# pandaLight.net
KiCad netlist of a schematic drawn in EAGLE
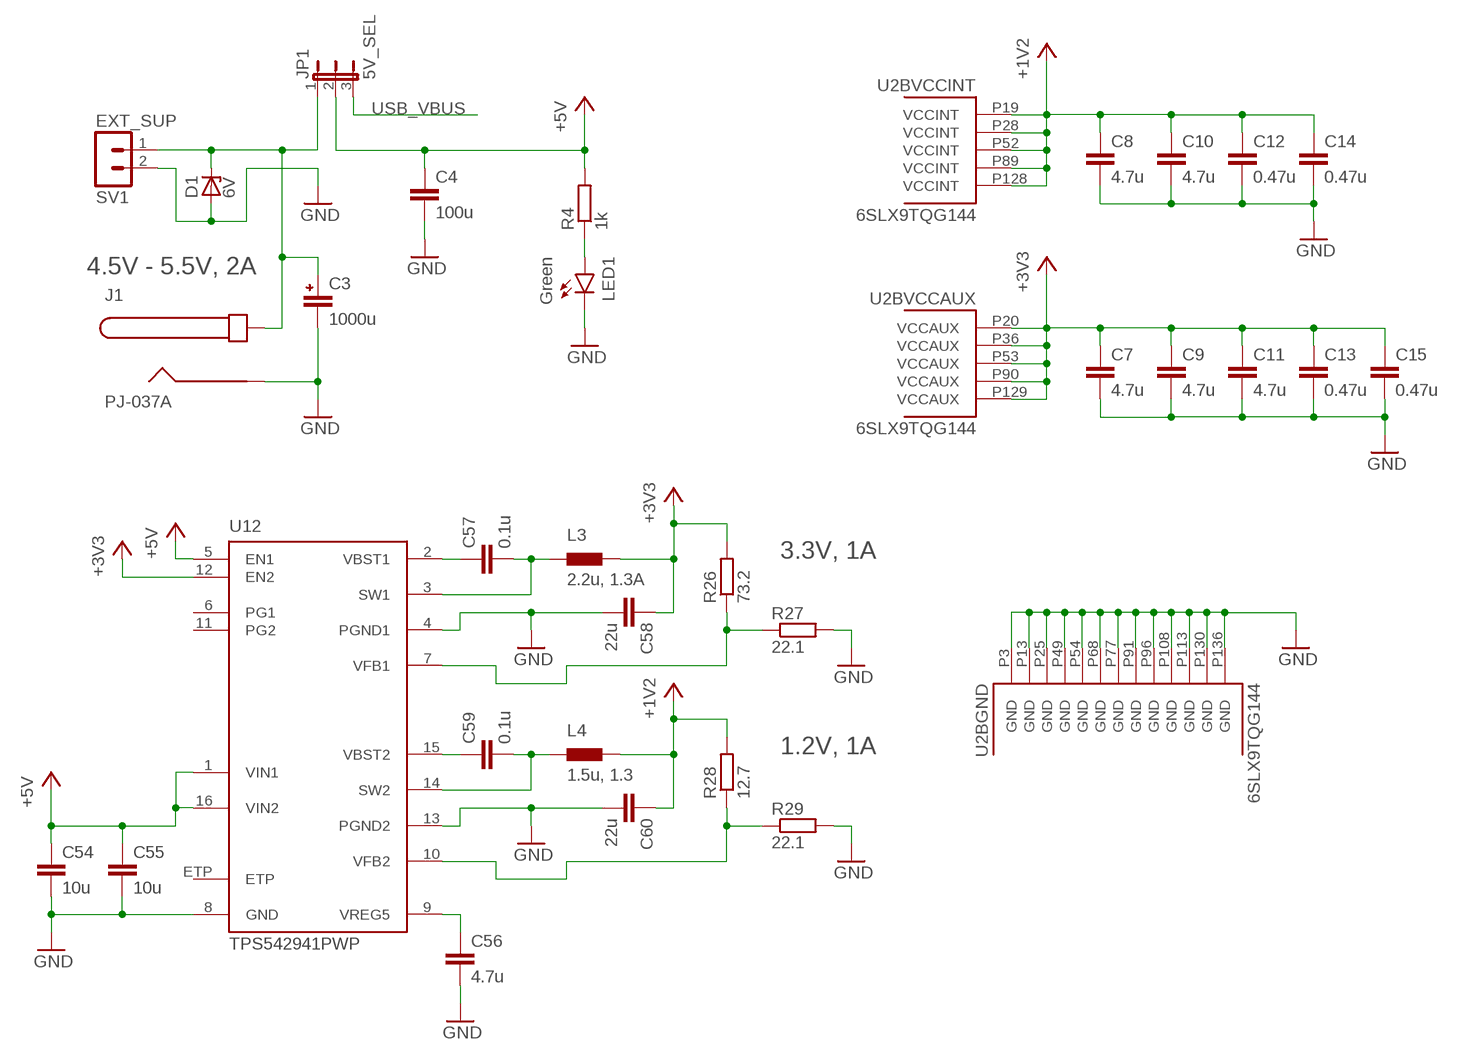
[diagram p0: schematic, sheet 1]
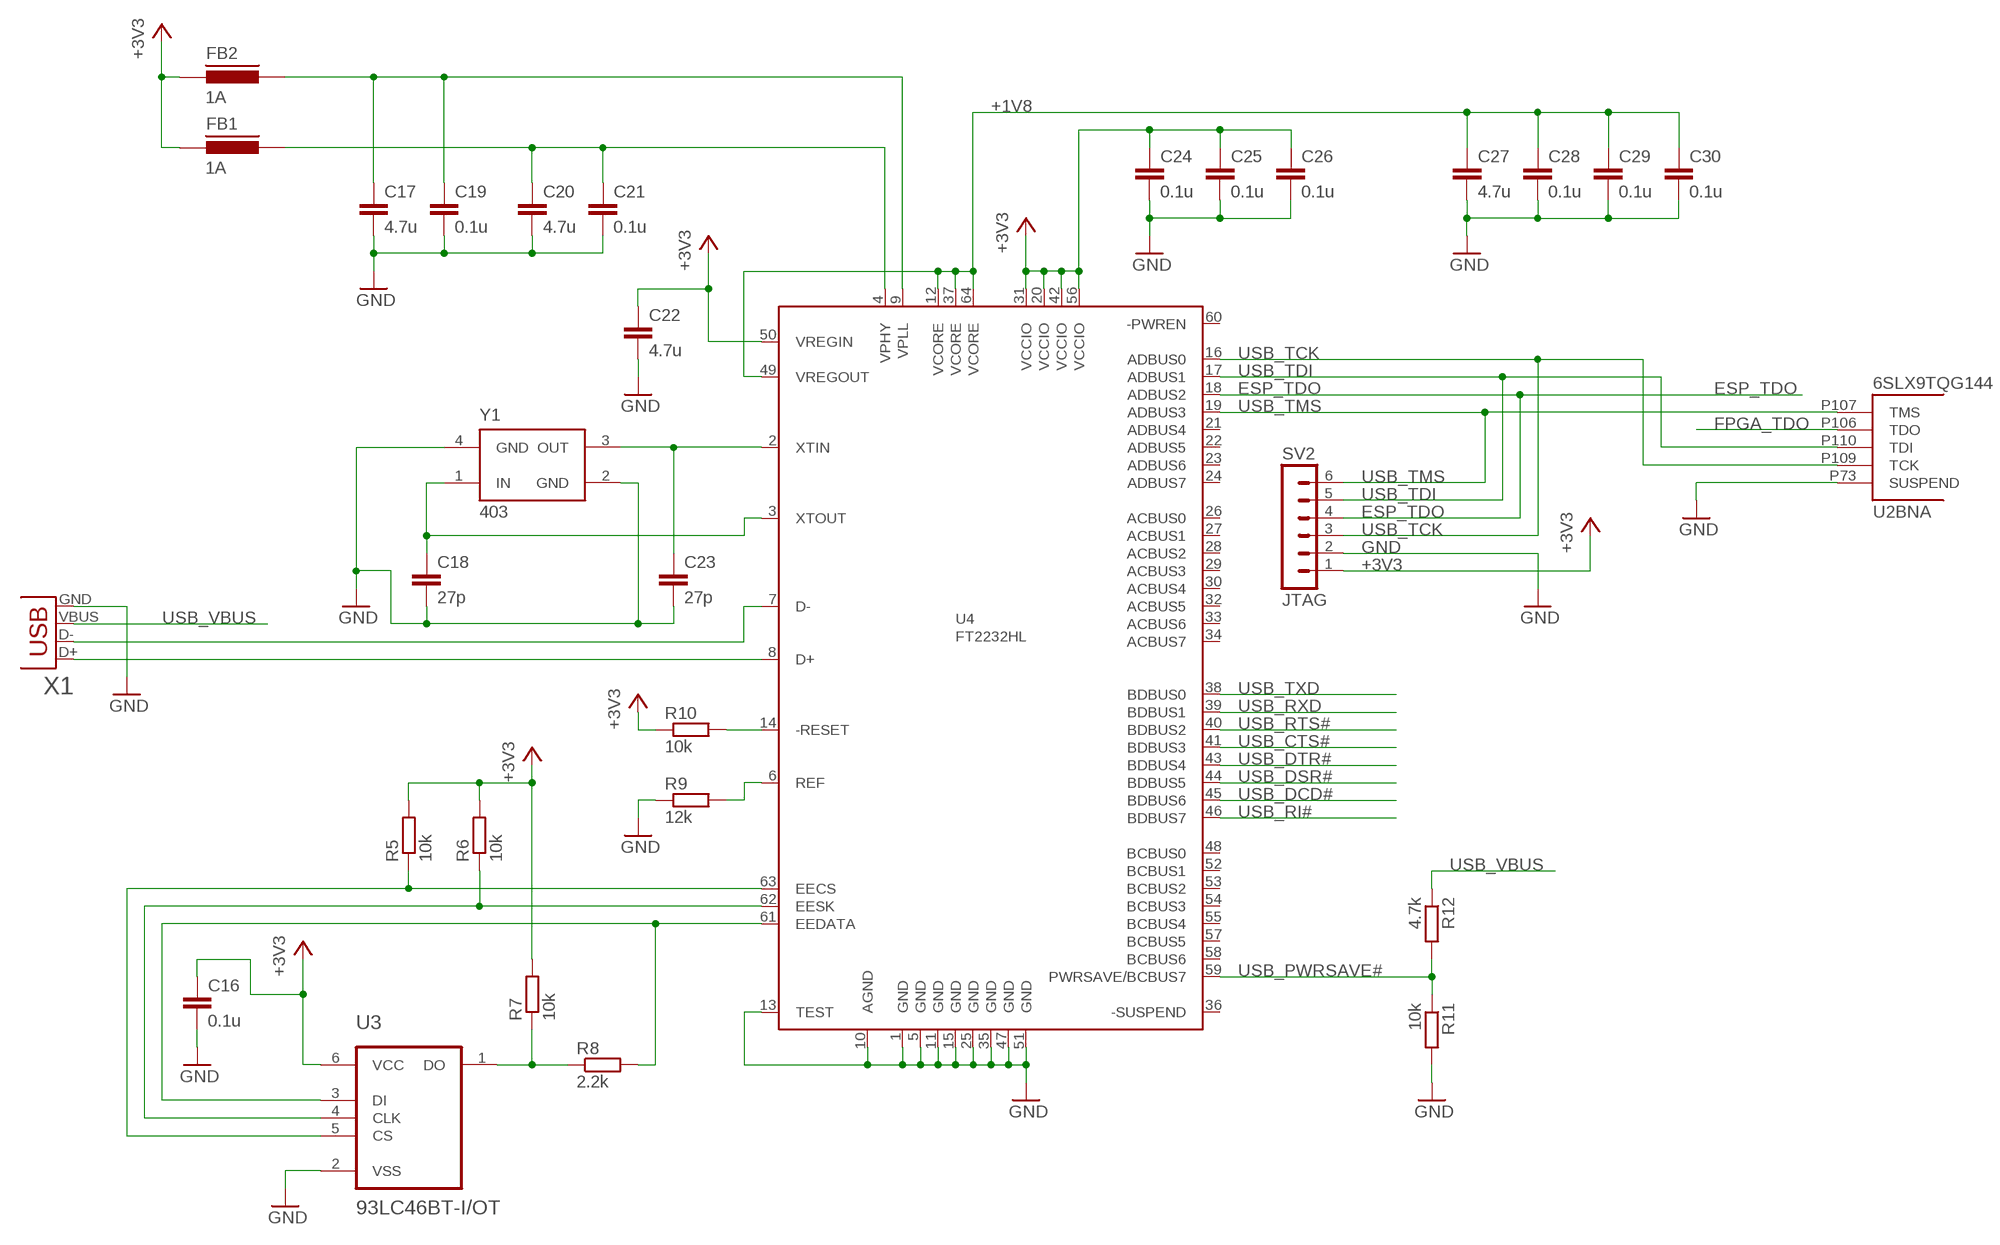
[diagram p1: schematic, sheet 2]
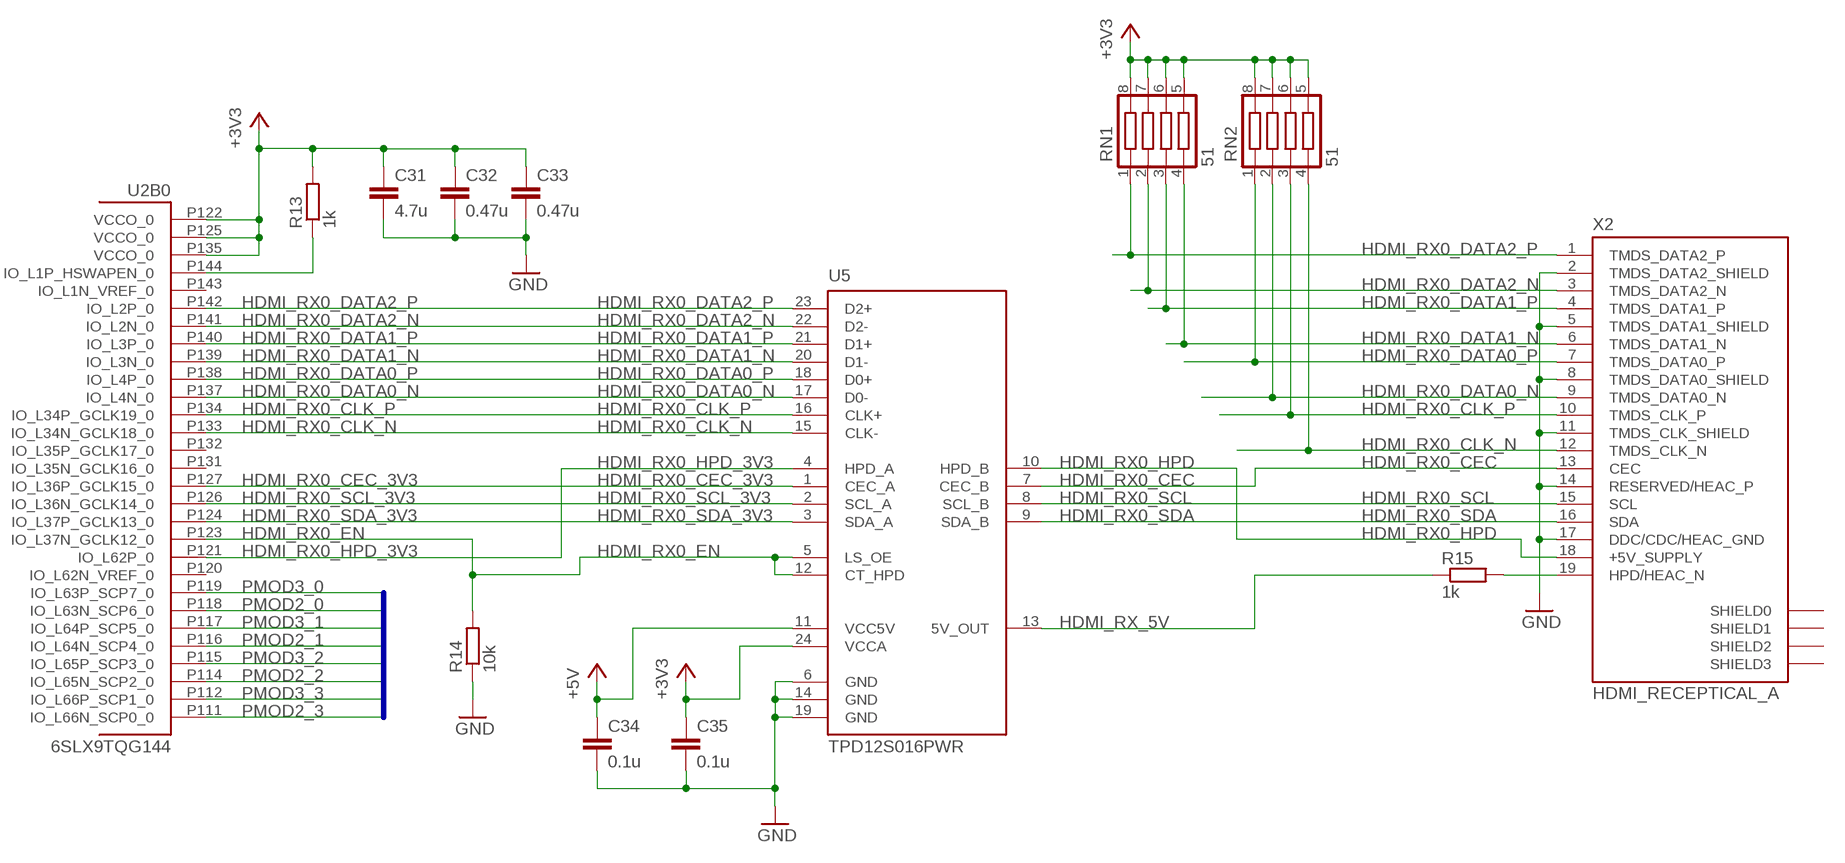
[diagram p2: schematic, sheet 3]
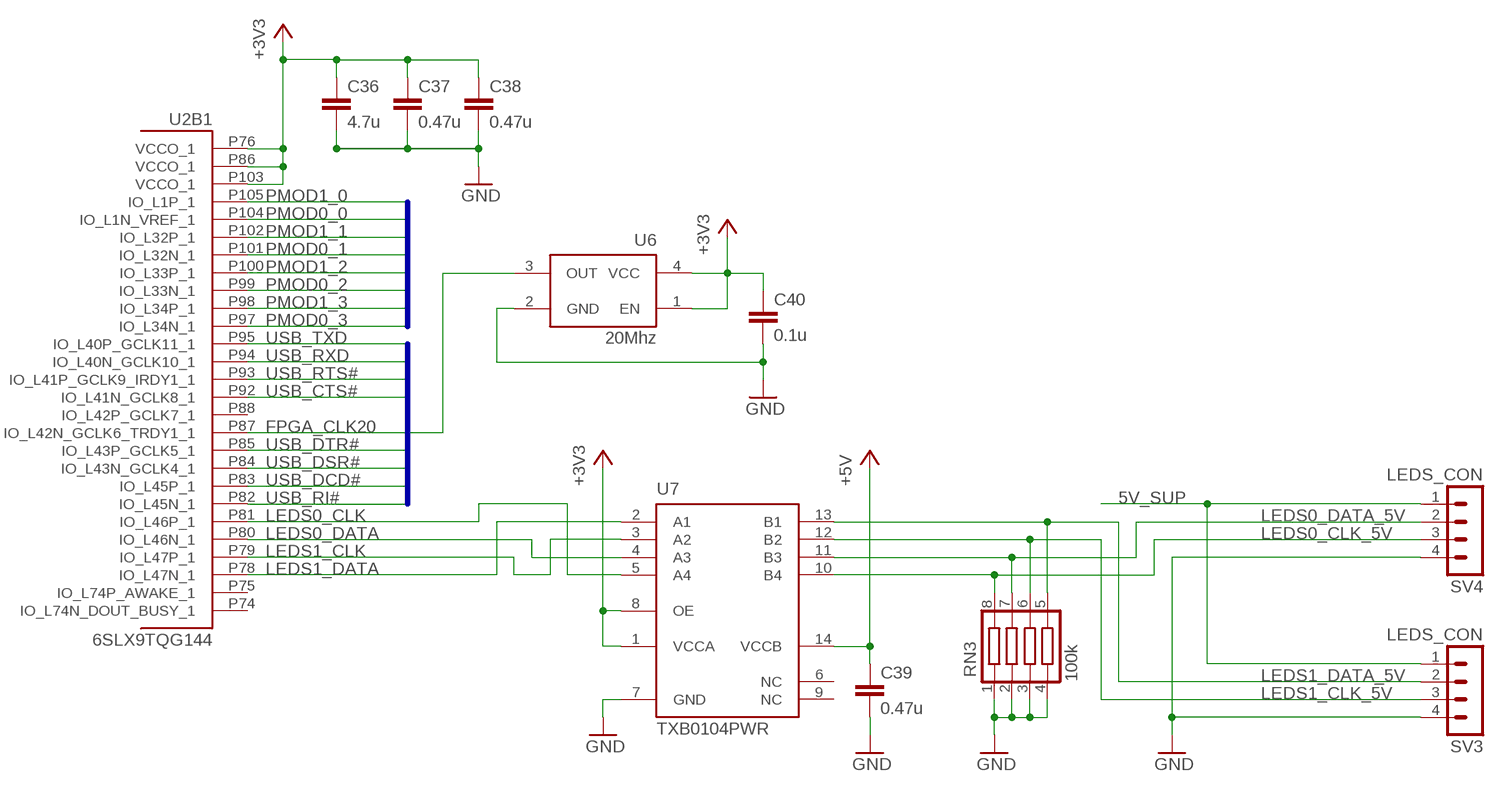
[diagram p3: schematic, sheet 4]
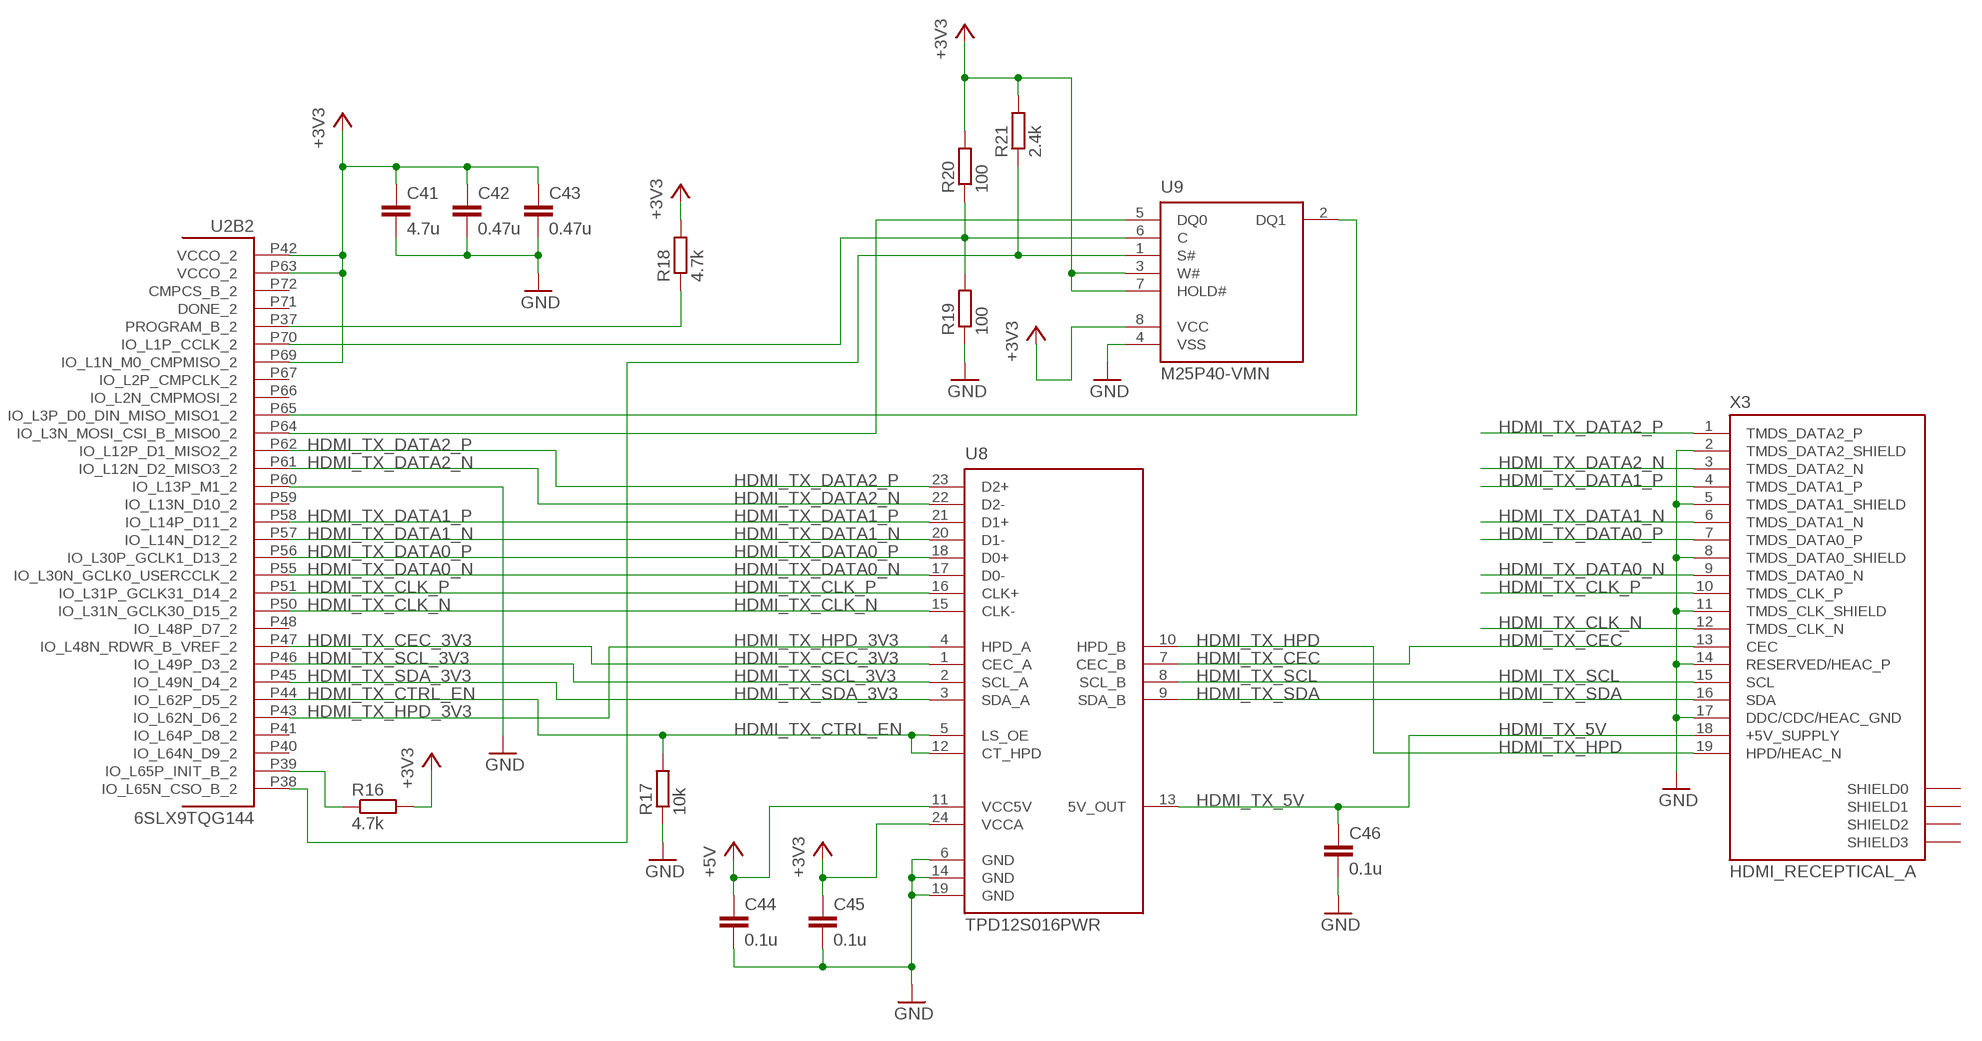
[diagram p4: schematic, sheet 5]
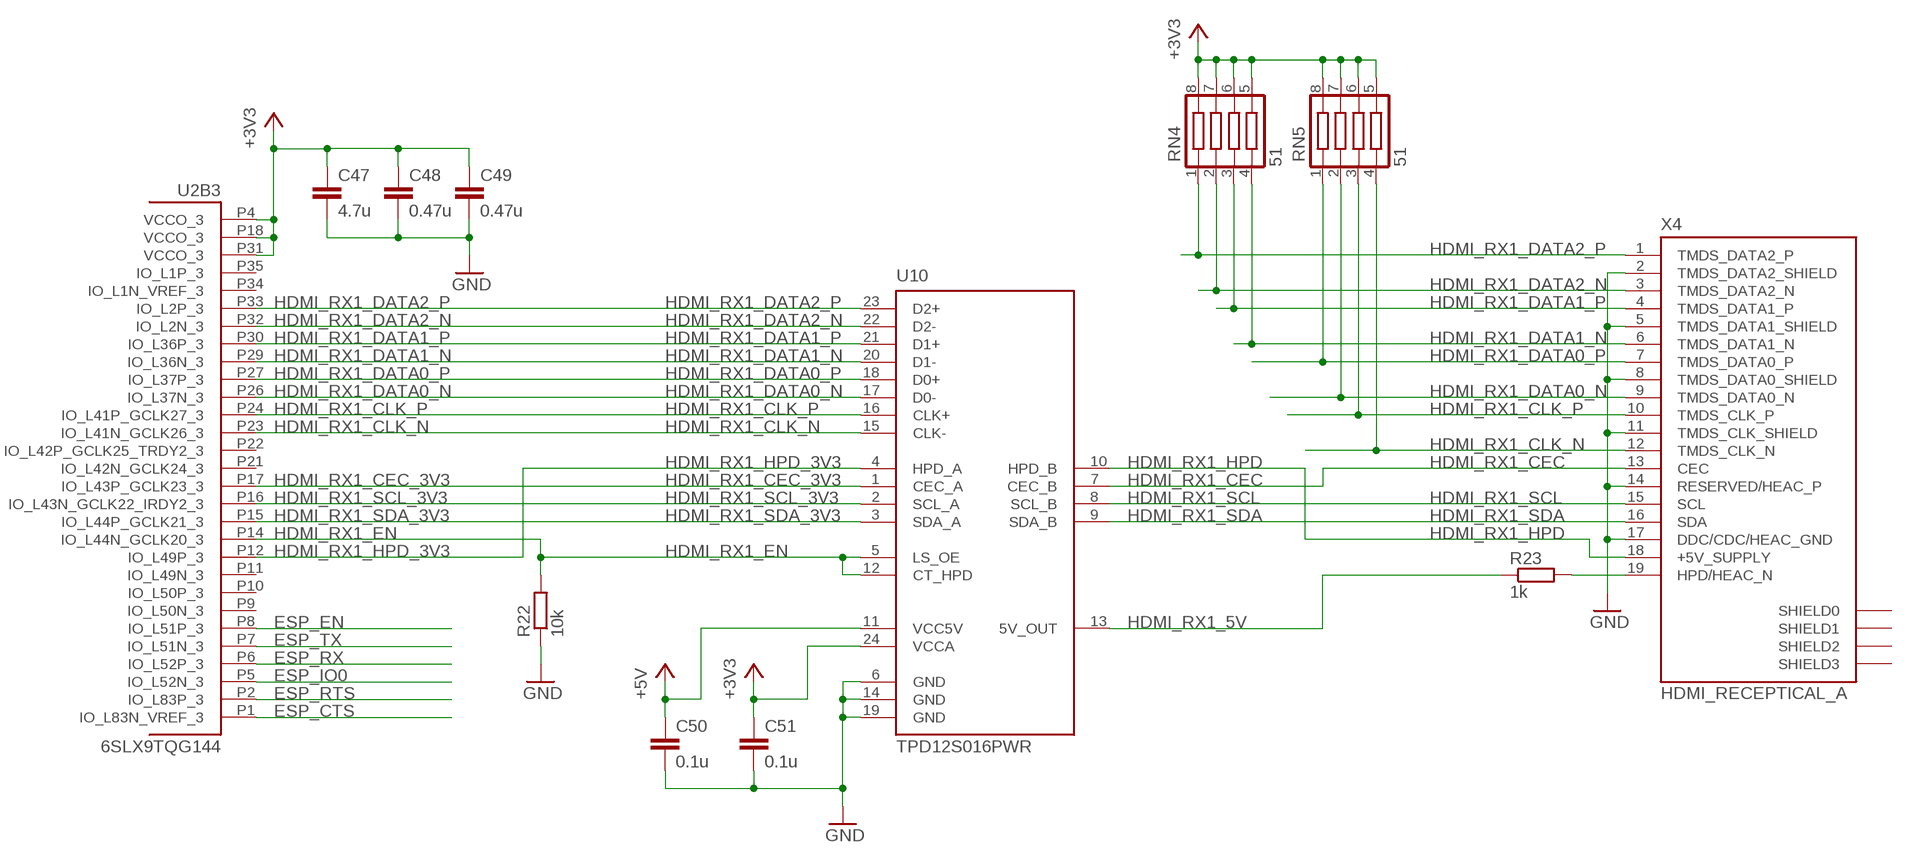
[diagram p5: schematic, sheet 6]
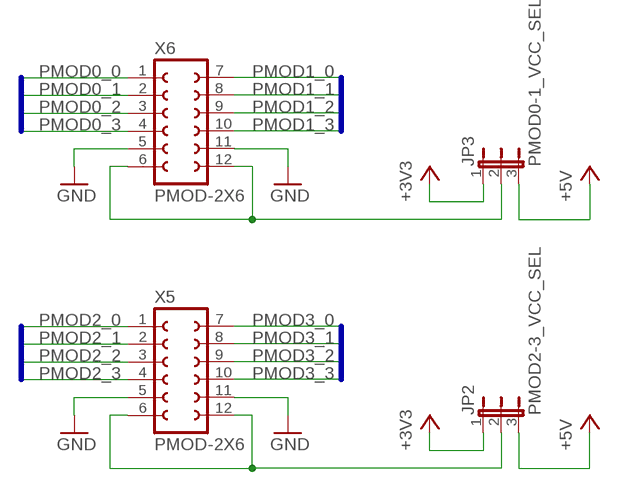
[diagram p6: schematic, sheet 7]
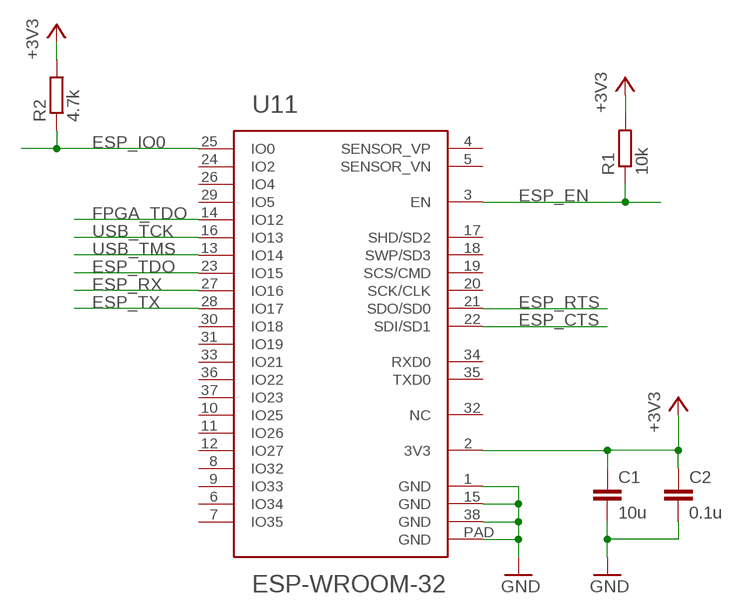
[diagram p7: schematic, sheet 8]
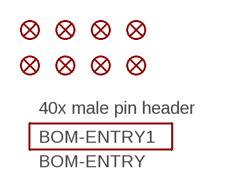
[diagram p8: schematic, sheet 9]

(export (version "E")
  (design (tool "Eeschema 10.0.6"))
  (components
    (comp (ref "C36")
      (value "4.7u")
      (footprint "eagle-import:C0603")
      (fields (field (name "PARTNO") "C0603C475K9PACTU"))
      (libsource (lib "eagle-import") (part "CAPACITOR0603"))
    )
    (comp (ref "C37")
      (value "0.47u")
      (footprint "eagle-import:C0402")
      (fields (field (name "PARTNO") "C1005X5R0J474K050BB"))
      (libsource (lib "eagle-import") (part "CAPACITOR0402"))
    )
    (comp (ref "C38")
      (value "0.47u")
      (footprint "eagle-import:C0402")
      (fields (field (name "PARTNO") "C1005X5R0J474K050BB"))
      (libsource (lib "eagle-import") (part "CAPACITOR0402"))
    )
    (comp (ref "C39")
      (value "0.47u")
      (footprint "eagle-import:C0402")
      (fields (field (name "PARTNO") "C1005X5R0J474K050BB"))
      (libsource (lib "eagle-import") (part "CAPACITOR0402"))
    )
    (comp (ref "C40")
      (value "0.1u")
      (footprint "eagle-import:C0402")
      (fields (field (name "PARTNO") "CL05B104KP5NNNC"))
      (libsource (lib "eagle-import") (part "CAPACITOR0402"))
    )
    (comp (ref "RN3")
      (value "100k")
      (footprint "eagle-import:741C083")
      (fields (field (name "PARTNO") "741C083104JP"))
      (libsource (lib "eagle-import") (part "741C083"))
    )
    (comp (ref "SV3")
      (value "LEDS_CON")
      (footprint "eagle-import:MA04-1")
      (libsource (lib "eagle-import") (part "MA04-1"))
    )
    (comp (ref "SV4")
      (value "LEDS_CON")
      (footprint "eagle-import:MA04-1")
      (libsource (lib "eagle-import") (part "MA04-1"))
    )
    (comp (ref "U2")
      (value "6SLX9TQG144")
      (footprint "eagle-import:TQ144")
      (fields (field (name "PARTNO") "XC6SLX9-3TQG144C"))
      (libsource (lib "eagle-import") (part "6SLX9TQG144"))
    )
    (comp (ref "U6")
      (value "20Mhz")
      (footprint "eagle-import:OSCI-1.6X1.2")
      (fields (field (name "PARTNO") "ASCO-20.000MHZ-EK-T3"))
      (libsource (lib "eagle-import") (part "OSCILLATOR"))
    )
    (comp (ref "U7")
      (value "TXB0104PWR")
      (footprint "eagle-import:R-PDSO-G14")
      (libsource (lib "eagle-import") (part "TXB0104PWR"))
    )
    (comp (ref "C41")
      (value "4.7u")
      (footprint "eagle-import:C0603")
      (fields (field (name "PARTNO") "C0603C475K9PACTU"))
      (libsource (lib "eagle-import") (part "CAPACITOR0603"))
    )
    (comp (ref "C42")
      (value "0.47u")
      (footprint "eagle-import:C0402")
      (fields (field (name "PARTNO") "C1005X5R0J474K050BB"))
      (libsource (lib "eagle-import") (part "CAPACITOR0402"))
    )
    (comp (ref "C43")
      (value "0.47u")
      (footprint "eagle-import:C0402")
      (fields (field (name "PARTNO") "C1005X5R0J474K050BB"))
      (libsource (lib "eagle-import") (part "CAPACITOR0402"))
    )
    (comp (ref "C44")
      (value "0.1u")
      (footprint "eagle-import:C0402")
      (fields (field (name "PARTNO") "CL05B104KP5NNNC"))
      (libsource (lib "eagle-import") (part "CAPACITOR0402"))
    )
    (comp (ref "C45")
      (value "0.1u")
      (footprint "eagle-import:C0402")
      (fields (field (name "PARTNO") "CL05B104KP5NNNC"))
      (libsource (lib "eagle-import") (part "CAPACITOR0402"))
    )
    (comp (ref "C46")
      (value "0.1u")
      (footprint "eagle-import:C0402")
      (fields (field (name "PARTNO") "CL05B104KP5NNNC"))
      (libsource (lib "eagle-import") (part "CAPACITOR0402"))
    )
    (comp (ref "R16")
      (value "4.7k")
      (footprint "eagle-import:R0402")
      (fields (field (name "PARTNO") "ERJ-2RKF4701X"))
      (libsource (lib "eagle-import") (part "RESISTOR0402"))
    )
    (comp (ref "R17")
      (value "10k")
      (footprint "eagle-import:R0402")
      (fields (field (name "PARTNO") "ERJ-2RKF1002X"))
      (libsource (lib "eagle-import") (part "RESISTOR0402"))
    )
    (comp (ref "R18")
      (value "4.7k")
      (footprint "eagle-import:R0402")
      (fields (field (name "PARTNO") "ERJ-2RKF4701X"))
      (libsource (lib "eagle-import") (part "RESISTOR0402"))
    )
    (comp (ref "R19")
      (value "100")
      (footprint "eagle-import:R0402")
      (fields (field (name "PARTNO") "ERJ-2GEJ101X"))
      (libsource (lib "eagle-import") (part "RESISTOR0402"))
    )
    (comp (ref "R20")
      (value "100")
      (footprint "eagle-import:R0402")
      (fields (field (name "PARTNO") "ERJ-2GEJ101X"))
      (libsource (lib "eagle-import") (part "RESISTOR0402"))
    )
    (comp (ref "R21")
      (value "2.4k")
      (footprint "eagle-import:R0402")
      (fields (field (name "PARTNO") "ERJ-2RKF2401X"))
      (libsource (lib "eagle-import") (part "RESISTOR0402"))
    )
    (comp (ref "U8")
      (value "TPD12S016PWR")
      (footprint "eagle-import:PW_R-PDSO-G24")
      (libsource (lib "eagle-import") (part "TPD12S016PWR"))
    )
    (comp (ref "U9")
      (value "M25P40-VMN")
      (footprint "eagle-import:SO8N")
      (fields (field (name "PARTNO") "M25P80-VMN6TP"))
      (libsource (lib "eagle-import") (part "M25P40-VMN"))
    )
    (comp (ref "X3")
      (value "HDMI_RECEPTICAL_A")
      (footprint "eagle-import:HDMI_TYPE_A_RECEPTICAL")
      (fields (field (name "PARTNO") "10029449-111RLF"))
      (libsource (lib "eagle-import") (part "HDMI_RECEPTICAL_A"))
    )
    (comp (ref "FID1")
      (value "FIDUCIAL1X2")
      (footprint "eagle-import:FIDUCIAL-1X2")
      (libsource (lib "eagle-import") (part "FIDUCIAL1X2"))
    )
    (comp (ref "FID2")
      (value "FIDUCIAL1X2")
      (footprint "eagle-import:FIDUCIAL-1X2")
      (libsource (lib "eagle-import") (part "FIDUCIAL1X2"))
    )
    (comp (ref "FID3")
      (value "FIDUCIAL1X2")
      (footprint "eagle-import:FIDUCIAL-1X2")
      (libsource (lib "eagle-import") (part "FIDUCIAL1X2"))
    )
    (comp (ref "FID4")
      (value "FIDUCIAL1X2")
      (footprint "eagle-import:FIDUCIAL-1X2")
      (libsource (lib "eagle-import") (part "FIDUCIAL1X2"))
    )
    (comp (ref "FID5")
      (value "FIDUCIAL1X2")
      (footprint "eagle-import:FIDUCIAL-1X2")
      (libsource (lib "eagle-import") (part "FIDUCIAL1X2"))
    )
    (comp (ref "FID6")
      (value "FIDUCIAL1X2")
      (footprint "eagle-import:FIDUCIAL-1X2")
      (libsource (lib "eagle-import") (part "FIDUCIAL1X2"))
    )
    (comp (ref "FID7")
      (value "FIDUCIAL1X2")
      (footprint "eagle-import:FIDUCIAL-1X2")
      (libsource (lib "eagle-import") (part "FIDUCIAL1X2"))
    )
    (comp (ref "FID8")
      (value "FIDUCIAL1X2")
      (footprint "eagle-import:FIDUCIAL-1X2")
      (libsource (lib "eagle-import") (part "FIDUCIAL1X2"))
    )
    (comp (ref "C3")
      (value "1000u")
      (footprint "eagle-import:MVY_HA0")
      (fields (field (name "PARTNO") "EMVY6R3ADA102MHA0G"))
      (libsource (lib "eagle-import") (part "CAPACITOR_POL"))
    )
    (comp (ref "C4")
      (value "100u")
      (footprint "eagle-import:C1206")
      (fields (field (name "PARTNO") "CL31A107MQHNNNE"))
      (libsource (lib "eagle-import") (part "CAPACITOR1206"))
    )
    (comp (ref "C7")
      (value "4.7u")
      (footprint "eagle-import:C0603")
      (fields (field (name "PARTNO") "C0603C475K9PACTU"))
      (libsource (lib "eagle-import") (part "CAPACITOR0603"))
    )
    (comp (ref "C8")
      (value "4.7u")
      (footprint "eagle-import:C0603")
      (fields (field (name "PARTNO") "C0603C475K9PACTU"))
      (libsource (lib "eagle-import") (part "CAPACITOR0603"))
    )
    (comp (ref "C9")
      (value "4.7u")
      (footprint "eagle-import:C0603")
      (fields (field (name "PARTNO") "C0603C475K9PACTU"))
      (libsource (lib "eagle-import") (part "CAPACITOR0603"))
    )
    (comp (ref "C10")
      (value "4.7u")
      (footprint "eagle-import:C0603")
      (fields (field (name "PARTNO") "C0603C475K9PACTU"))
      (libsource (lib "eagle-import") (part "CAPACITOR0603"))
    )
    (comp (ref "C11")
      (value "4.7u")
      (footprint "eagle-import:C0603")
      (fields (field (name "PARTNO") "C0603C475K9PACTU"))
      (libsource (lib "eagle-import") (part "CAPACITOR0603"))
    )
    (comp (ref "C12")
      (value "0.47u")
      (footprint "eagle-import:C0402")
      (fields (field (name "PARTNO") "C1005X5R0J474K050BB"))
      (libsource (lib "eagle-import") (part "CAPACITOR0402"))
    )
    (comp (ref "C13")
      (value "0.47u")
      (footprint "eagle-import:C0402")
      (fields (field (name "PARTNO") "C1005X5R0J474K050BB"))
      (libsource (lib "eagle-import") (part "CAPACITOR0402"))
    )
    (comp (ref "C14")
      (value "0.47u")
      (footprint "eagle-import:C0402")
      (fields (field (name "PARTNO") "C1005X5R0J474K050BB"))
      (libsource (lib "eagle-import") (part "CAPACITOR0402"))
    )
    (comp (ref "C15")
      (value "0.47u")
      (footprint "eagle-import:C0402")
      (fields (field (name "PARTNO") "C1005X5R0J474K050BB"))
      (libsource (lib "eagle-import") (part "CAPACITOR0402"))
    )
    (comp (ref "C54")
      (value "10u")
      (footprint "eagle-import:C0603")
      (fields (field (name "PARTNO") "CL10A106MQ8NNNC"))
      (libsource (lib "eagle-import") (part "CAPACITOR0603"))
    )
    (comp (ref "C55")
      (value "10u")
      (footprint "eagle-import:C0603")
      (fields (field (name "PARTNO") "CL10A106MQ8NNNC"))
      (libsource (lib "eagle-import") (part "CAPACITOR0603"))
    )
    (comp (ref "C56")
      (value "4.7u")
      (footprint "eagle-import:C0603")
      (fields (field (name "PARTNO") "C0603C475K9PACTU"))
      (libsource (lib "eagle-import") (part "CAPACITOR0603"))
    )
    (comp (ref "C57")
      (value "0.1u")
      (footprint "eagle-import:C0402")
      (fields (field (name "PARTNO") "CL05B104KP5NNNC"))
      (libsource (lib "eagle-import") (part "CAPACITOR0402"))
    )
    (comp (ref "C58")
      (value "22u")
      (footprint "eagle-import:C0603")
      (fields (field (name "PARTNO") "CL10A226MQ8NRNC"))
      (libsource (lib "eagle-import") (part "CAPACITOR0603"))
    )
    (comp (ref "C59")
      (value "0.1u")
      (footprint "eagle-import:C0402")
      (fields (field (name "PARTNO") "CL05B104KP5NNNC"))
      (libsource (lib "eagle-import") (part "CAPACITOR0402"))
    )
    (comp (ref "C60")
      (value "22u")
      (footprint "eagle-import:C0603")
      (fields (field (name "PARTNO") "CL10A226MQ8NRNC"))
      (libsource (lib "eagle-import") (part "CAPACITOR0603"))
    )
    (comp (ref "D1")
      (value "6V")
      (footprint "eagle-import:DO-214AC")
      (fields (field (name "PARTNO") "SMAJ6.0A"))
      (libsource (lib "eagle-import") (part "ZENER_DIODE"))
    )
    (comp (ref "J1")
      (value "PJ-037A")
      (footprint "eagle-import:PJ-037A")
      (libsource (lib "eagle-import") (part "PJ-037A"))
    )
    (comp (ref "JP1")
      (value "5V_SEL")
      (footprint "eagle-import:JP2")
      (fields (field (name "PARTNO") "SPC02SYAN"))
      (libsource (lib "eagle-import") (part "JP2E"))
    )
    (comp (ref "L3")
      (value "2.2u, 1.3A")
      (footprint "eagle-import:SRN3015_3X3")
      (fields (field (name "PARTNO") "SRN3015-2R2M"))
      (libsource (lib "eagle-import") (part "SRN3015"))
    )
    (comp (ref "L4")
      (value "1.5u, 1.3")
      (footprint "eagle-import:SRN3015_3X3")
      (fields (field (name "PARTNO") "SRN3015-1R5Y"))
      (libsource (lib "eagle-import") (part "SRN3015"))
    )
    (comp (ref "LED1")
      (value "Green")
      (footprint "eagle-import:LED-0603")
      (fields (field (name "PARTNO") "LTST-C191KGKT"))
      (libsource (lib "eagle-import") (part "LED0603"))
    )
    (comp (ref "R4")
      (value "1k")
      (footprint "eagle-import:R0402")
      (fields (field (name "PARTNO") "ERJ-2RKF1001X"))
      (libsource (lib "eagle-import") (part "RESISTOR0402"))
    )
    (comp (ref "R26")
      (value "73.2")
      (footprint "eagle-import:R0402")
      (fields (field (name "PARTNO") "ERJ-2RKF73R2X"))
      (libsource (lib "eagle-import") (part "RESISTOR0402"))
    )
    (comp (ref "R27")
      (value "22.1")
      (footprint "eagle-import:R0402")
      (fields (field (name "PARTNO") "ERJ-2RKF22R1X"))
      (libsource (lib "eagle-import") (part "RESISTOR0402"))
    )
    (comp (ref "R28")
      (value "12.7")
      (footprint "eagle-import:R0402")
      (fields (field (name "PARTNO") "ERJ-2RKF12R7X"))
      (libsource (lib "eagle-import") (part "RESISTOR0402"))
    )
    (comp (ref "R29")
      (value "22.1")
      (footprint "eagle-import:R0402")
      (fields (field (name "PARTNO") "ERJ-2RKF22R1X"))
      (libsource (lib "eagle-import") (part "RESISTOR0402"))
    )
    (comp (ref "SV1")
      (value "EXT_SUP")
      (footprint "eagle-import:MA02-1")
      (libsource (lib "eagle-import") (part "MA02-1"))
    )
    (comp (ref "U12")
      (value "TPS542941PWP")
      (footprint "eagle-import:R-PDSO-G16")
      (libsource (lib "eagle-import") (part "TPS542941PWP"))
    )
    (comp (ref "C1")
      (value "10u")
      (footprint "eagle-import:C0603")
      (libsource (lib "eagle-import") (part "CAPACITOR0603"))
    )
    (comp (ref "C2")
      (value "0.1u")
      (footprint "eagle-import:C0402")
      (fields (field (name "PARTNO") "CL05B104KP5NNNC"))
      (libsource (lib "eagle-import") (part "CAPACITOR0402"))
    )
    (comp (ref "R1")
      (value "10k")
      (footprint "eagle-import:R0402")
      (fields (field (name "PARTNO") "ERJ-2RKF1002X"))
      (libsource (lib "eagle-import") (part "RESISTOR0402"))
    )
    (comp (ref "R2")
      (value "4.7k")
      (footprint "eagle-import:R0402")
      (fields (field (name "PARTNO") "ERJ-2RKF1002X"))
      (libsource (lib "eagle-import") (part "RESISTOR0402"))
    )
    (comp (ref "U11")
      (value "ESP-WROOM-32")
      (footprint "eagle-import:ESP-WROOM-32")
      (libsource (lib "eagle-import") (part "ESP-WROOM-32"))
    )
    (comp (ref "C31")
      (value "4.7u")
      (footprint "eagle-import:C0603")
      (fields (field (name "PARTNO") "C0603C475K9PACTU"))
      (libsource (lib "eagle-import") (part "CAPACITOR0603"))
    )
    (comp (ref "C32")
      (value "0.47u")
      (footprint "eagle-import:C0402")
      (fields (field (name "PARTNO") "C1005X5R0J474K050BB"))
      (libsource (lib "eagle-import") (part "CAPACITOR0402"))
    )
    (comp (ref "C33")
      (value "0.47u")
      (footprint "eagle-import:C0402")
      (fields (field (name "PARTNO") "C1005X5R0J474K050BB"))
      (libsource (lib "eagle-import") (part "CAPACITOR0402"))
    )
    (comp (ref "C34")
      (value "0.1u")
      (footprint "eagle-import:C0402")
      (fields (field (name "PARTNO") "CL05B104KP5NNNC"))
      (libsource (lib "eagle-import") (part "CAPACITOR0402"))
    )
    (comp (ref "C35")
      (value "0.1u")
      (footprint "eagle-import:C0402")
      (fields (field (name "PARTNO") "CL05B104KP5NNNC"))
      (libsource (lib "eagle-import") (part "CAPACITOR0402"))
    )
    (comp (ref "R13")
      (value "1k")
      (footprint "eagle-import:R0402")
      (fields (field (name "PARTNO") "ERJ-2RKF1001X"))
      (libsource (lib "eagle-import") (part "RESISTOR0402"))
    )
    (comp (ref "R14")
      (value "10k")
      (footprint "eagle-import:R0402")
      (fields (field (name "PARTNO") "ERJ-2RKF1002X"))
      (libsource (lib "eagle-import") (part "RESISTOR0402"))
    )
    (comp (ref "R15")
      (value "1k")
      (footprint "eagle-import:R0402")
      (fields (field (name "PARTNO") "ERJ-2RKF1001X"))
      (libsource (lib "eagle-import") (part "RESISTOR0402"))
    )
    (comp (ref "RN1")
      (value "51")
      (footprint "eagle-import:741C083")
      (fields (field (name "PARTNO") "741C083510JP"))
      (libsource (lib "eagle-import") (part "741C083"))
    )
    (comp (ref "RN2")
      (value "51")
      (footprint "eagle-import:741C083")
      (fields (field (name "PARTNO") "741C083510JP"))
      (libsource (lib "eagle-import") (part "741C083"))
    )
    (comp (ref "U5")
      (value "TPD12S016PWR")
      (footprint "eagle-import:PW_R-PDSO-G24")
      (libsource (lib "eagle-import") (part "TPD12S016PWR"))
    )
    (comp (ref "X2")
      (value "HDMI_RECEPTICAL_A")
      (footprint "eagle-import:HDMI_TYPE_A_RECEPTICAL")
      (fields (field (name "PARTNO") "10029449-111RLF"))
      (libsource (lib "eagle-import") (part "HDMI_RECEPTICAL_A"))
    )
    (comp (ref "C47")
      (value "4.7u")
      (footprint "eagle-import:C0603")
      (fields (field (name "PARTNO") "C0603C475K9PACTU"))
      (libsource (lib "eagle-import") (part "CAPACITOR0603"))
    )
    (comp (ref "C48")
      (value "0.47u")
      (footprint "eagle-import:C0402")
      (fields (field (name "PARTNO") "C1005X5R0J474K050BB"))
      (libsource (lib "eagle-import") (part "CAPACITOR0402"))
    )
    (comp (ref "C49")
      (value "0.47u")
      (footprint "eagle-import:C0402")
      (fields (field (name "PARTNO") "C1005X5R0J474K050BB"))
      (libsource (lib "eagle-import") (part "CAPACITOR0402"))
    )
    (comp (ref "C50")
      (value "0.1u")
      (footprint "eagle-import:C0402")
      (fields (field (name "PARTNO") "CL05B104KP5NNNC"))
      (libsource (lib "eagle-import") (part "CAPACITOR0402"))
    )
    (comp (ref "C51")
      (value "0.1u")
      (footprint "eagle-import:C0402")
      (fields (field (name "PARTNO") "CL05B104KP5NNNC"))
      (libsource (lib "eagle-import") (part "CAPACITOR0402"))
    )
    (comp (ref "R22")
      (value "10k")
      (footprint "eagle-import:R0402")
      (fields (field (name "PARTNO") "ERJ-2RKF1002X"))
      (libsource (lib "eagle-import") (part "RESISTOR0402"))
    )
    (comp (ref "R23")
      (value "1k")
      (footprint "eagle-import:R0402")
      (fields (field (name "PARTNO") "ERJ-2RKF1001X"))
      (libsource (lib "eagle-import") (part "RESISTOR0402"))
    )
    (comp (ref "RN4")
      (value "51")
      (footprint "eagle-import:741C083")
      (fields (field (name "PARTNO") "741C083510JP"))
      (libsource (lib "eagle-import") (part "741C083"))
    )
    (comp (ref "RN5")
      (value "51")
      (footprint "eagle-import:741C083")
      (fields (field (name "PARTNO") "741C083510JP"))
      (libsource (lib "eagle-import") (part "741C083"))
    )
    (comp (ref "U10")
      (value "TPD12S016PWR")
      (footprint "eagle-import:PW_R-PDSO-G24")
      (libsource (lib "eagle-import") (part "TPD12S016PWR"))
    )
    (comp (ref "X4")
      (value "HDMI_RECEPTICAL_A")
      (footprint "eagle-import:HDMI_TYPE_A_RECEPTICAL")
      (fields (field (name "PARTNO") "10029449-111RLF"))
      (libsource (lib "eagle-import") (part "HDMI_RECEPTICAL_A"))
    )
    (comp (ref "JP2")
      (value "PMOD2-3_VCC_SEL")
      (footprint "eagle-import:JP2")
      (fields (field (name "PARTNO") "SPC02SYAN"))
      (libsource (lib "eagle-import") (part "JP2E"))
    )
    (comp (ref "JP3")
      (value "PMOD0-1_VCC_SEL")
      (footprint "eagle-import:JP2")
      (fields (field (name "PARTNO") "SPC02SYAN"))
      (libsource (lib "eagle-import") (part "JP2E"))
    )
    (comp (ref "X5")
      (value "PMOD-2X6")
      (footprint "eagle-import:PMOD-2X6")
      (fields (field (name "PARTNO") "PPTC062LJBN-RC"))
      (libsource (lib "eagle-import") (part "PMOD-2X6"))
    )
    (comp (ref "X6")
      (value "PMOD-2X6")
      (footprint "eagle-import:PMOD-2X6")
      (fields (field (name "PARTNO") "PPTC062LJBN-RC"))
      (libsource (lib "eagle-import") (part "PMOD-2X6"))
    )
    (comp (ref "C16")
      (value "0.1u")
      (footprint "eagle-import:C0402")
      (fields (field (name "PARTNO") "CL05B104KP5NNNC"))
      (libsource (lib "eagle-import") (part "CAPACITOR0402"))
    )
    (comp (ref "C17")
      (value "4.7u")
      (footprint "eagle-import:C0603")
      (fields (field (name "PARTNO") "C0603C475K9PACTU"))
      (libsource (lib "eagle-import") (part "CAPACITOR0603"))
    )
    (comp (ref "C18")
      (value "27p")
      (footprint "eagle-import:C0402")
      (fields (field (name "PARTNO") "CL05C270JB5NNNC"))
      (libsource (lib "eagle-import") (part "CAPACITOR0402"))
    )
    (comp (ref "C19")
      (value "0.1u")
      (footprint "eagle-import:C0402")
      (fields (field (name "PARTNO") "CL05B104KP5NNNC"))
      (libsource (lib "eagle-import") (part "CAPACITOR0402"))
    )
    (comp (ref "C20")
      (value "4.7u")
      (footprint "eagle-import:C0603")
      (fields (field (name "PARTNO") "C0603C475K9PACTU"))
      (libsource (lib "eagle-import") (part "CAPACITOR0603"))
    )
    (comp (ref "C21")
      (value "0.1u")
      (footprint "eagle-import:C0402")
      (fields (field (name "PARTNO") "CL05B104KP5NNNC"))
      (libsource (lib "eagle-import") (part "CAPACITOR0402"))
    )
    (comp (ref "C22")
      (value "4.7u")
      (footprint "eagle-import:C0603")
      (fields (field (name "PARTNO") "C0603C475K9PACTU"))
      (libsource (lib "eagle-import") (part "CAPACITOR0603"))
    )
    (comp (ref "C23")
      (value "27p")
      (footprint "eagle-import:C0402")
      (fields (field (name "PARTNO") "CL05C270JB5NNNC"))
      (libsource (lib "eagle-import") (part "CAPACITOR0402"))
    )
    (comp (ref "C24")
      (value "0.1u")
      (footprint "eagle-import:C0402")
      (fields (field (name "PARTNO") "CL05B104KP5NNNC"))
      (libsource (lib "eagle-import") (part "CAPACITOR0402"))
    )
    (comp (ref "C25")
      (value "0.1u")
      (footprint "eagle-import:C0402")
      (fields (field (name "PARTNO") "CL05B104KP5NNNC"))
      (libsource (lib "eagle-import") (part "CAPACITOR0402"))
    )
    (comp (ref "C26")
      (value "0.1u")
      (footprint "eagle-import:C0402")
      (fields (field (name "PARTNO") "CL05B104KP5NNNC"))
      (libsource (lib "eagle-import") (part "CAPACITOR0402"))
    )
    (comp (ref "C27")
      (value "4.7u")
      (footprint "eagle-import:C0603")
      (fields (field (name "PARTNO") "C0603C475K9PACTU"))
      (libsource (lib "eagle-import") (part "CAPACITOR0603"))
    )
    (comp (ref "C28")
      (value "0.1u")
      (footprint "eagle-import:C0402")
      (fields (field (name "PARTNO") "CL05B104KP5NNNC"))
      (libsource (lib "eagle-import") (part "CAPACITOR0402"))
    )
    (comp (ref "C29")
      (value "0.1u")
      (footprint "eagle-import:C0402")
      (fields (field (name "PARTNO") "CL05B104KP5NNNC"))
      (libsource (lib "eagle-import") (part "CAPACITOR0402"))
    )
    (comp (ref "C30")
      (value "0.1u")
      (footprint "eagle-import:C0402")
      (fields (field (name "PARTNO") "CL05B104KP5NNNC"))
      (libsource (lib "eagle-import") (part "CAPACITOR0402"))
    )
    (comp (ref "FB1")
      (value "1A")
      (footprint "eagle-import:FB0402")
      (fields (field (name "PARTNO") "BK1005HS100-T"))
      (libsource (lib "eagle-import") (part "FERRITE0402"))
    )
    (comp (ref "FB2")
      (value "1A")
      (footprint "eagle-import:FB0402")
      (fields (field (name "PARTNO") "BK1005HS100-T"))
      (libsource (lib "eagle-import") (part "FERRITE0402"))
    )
    (comp (ref "R5")
      (value "10k")
      (footprint "eagle-import:R0402")
      (fields (field (name "PARTNO") "ERJ-2RKF1002X"))
      (libsource (lib "eagle-import") (part "RESISTOR0402"))
    )
    (comp (ref "R6")
      (value "10k")
      (footprint "eagle-import:R0402")
      (fields (field (name "PARTNO") "ERJ-2RKF1002X"))
      (libsource (lib "eagle-import") (part "RESISTOR0402"))
    )
    (comp (ref "R7")
      (value "10k")
      (footprint "eagle-import:R0402")
      (fields (field (name "PARTNO") "ERJ-2RKF1002X"))
      (libsource (lib "eagle-import") (part "RESISTOR0402"))
    )
    (comp (ref "R8")
      (value "2.2k")
      (footprint "eagle-import:R0402")
      (fields (field (name "PARTNO") "ERJ-2RKF2201X"))
      (libsource (lib "eagle-import") (part "RESISTOR0402"))
    )
    (comp (ref "R9")
      (value "12k")
      (footprint "eagle-import:R0402")
      (fields (field (name "PARTNO") "ERJ-2RKF1202X"))
      (libsource (lib "eagle-import") (part "RESISTOR0402"))
    )
    (comp (ref "R10")
      (value "10k")
      (footprint "eagle-import:R0402")
      (fields (field (name "PARTNO") "ERJ-2RKF1002X"))
      (libsource (lib "eagle-import") (part "RESISTOR0402"))
    )
    (comp (ref "R11")
      (value "10k")
      (footprint "eagle-import:R0402")
      (fields (field (name "PARTNO") "ERJ-2RKF1002X"))
      (libsource (lib "eagle-import") (part "RESISTOR0402"))
    )
    (comp (ref "R12")
      (value "4.7k")
      (footprint "eagle-import:R0402")
      (fields (field (name "PARTNO") "ERJ-2RKF4701X"))
      (libsource (lib "eagle-import") (part "RESISTOR0402"))
    )
    (comp (ref "SV2")
      (value "JTAG")
      (footprint "eagle-import:MA06-1")
      (libsource (lib "eagle-import") (part "MA06-1"))
    )
    (comp (ref "U3")
      (value "93LC46BT-I/OT")
      (footprint "eagle-import:SOT23-6")
      (libsource (lib "eagle-import") (part "93LC46BT-I/OT"))
    )
    (comp (ref "U4")
      (value "FT2232HL")
      (footprint "eagle-import:LQFP64")
      (fields (field (name "PARTNO") "FT2232HL-REEL"))
      (libsource (lib "eagle-import") (part "FT2232HL"))
    )
    (comp (ref "X1")
      (value "USBUB-S")
      (footprint "eagle-import:USB-UB-S")
      (fields (field (name "PARTNO") "10118192-0001LF"))
      (libsource (lib "eagle-import") (part "USBUB-S"))
    )
    (comp (ref "Y1")
      (value "403")
      (footprint "eagle-import:403-3.2X2.5")
      (fields (field (name "PARTNO") "403C35D12M00000"))
      (libsource (lib "eagle-import") (part "403"))
    )
  )
  (nets
    (net (code "1") (name "+1V2") (class "Default")
      (node (ref "C10") (pin "1") (pinfunction "1_1") (pintype "passive"))
      (node (ref "C12") (pin "1") (pinfunction "1_1") (pintype "passive"))
      (node (ref "C14") (pin "1") (pinfunction "1_1") (pintype "passive"))
      (node (ref "C60") (pin "1") (pinfunction "1_1") (pintype "passive"))
      (node (ref "C8") (pin "1") (pinfunction "1_1") (pintype "passive"))
      (node (ref "L4") (pin "2") (pinfunction "2_2") (pintype "passive"))
      (node (ref "R28") (pin "2") (pinfunction "2_2") (pintype "passive"))
      (node (ref "U2") (pin "P128") (pinfunction "VCCINT_P128") (pintype "input"))
      (node (ref "U2") (pin "P19") (pinfunction "VCCINT_P19") (pintype "input"))
      (node (ref "U2") (pin "P28") (pinfunction "VCCINT_P28") (pintype "input"))
      (node (ref "U2") (pin "P52") (pinfunction "VCCINT_P52") (pintype "input"))
      (node (ref "U2") (pin "P89") (pinfunction "VCCINT_P89") (pintype "input"))
    )
    (net (code "2") (name "+1V8") (class "Default")
      (node (ref "C27") (pin "1") (pinfunction "1_1") (pintype "passive"))
      (node (ref "C28") (pin "1") (pinfunction "1_1") (pintype "passive"))
      (node (ref "C29") (pin "1") (pinfunction "1_1") (pintype "passive"))
      (node (ref "C30") (pin "1") (pinfunction "1_1") (pintype "passive"))
      (node (ref "U4") (pin "12") (pinfunction "VCORE_12") (pintype "power_in"))
      (node (ref "U4") (pin "37") (pinfunction "VCORE_37") (pintype "power_in"))
      (node (ref "U4") (pin "49") (pinfunction "VREGOUT_49") (pintype "output"))
      (node (ref "U4") (pin "64") (pinfunction "VCORE_64") (pintype "power_in"))
    )
    (net (code "3") (name "+3V3") (class "Default")
      (node (ref "C1") (pin "1") (pinfunction "1_1") (pintype "passive"))
      (node (ref "C11") (pin "1") (pinfunction "1_1") (pintype "passive"))
      (node (ref "C13") (pin "1") (pinfunction "1_1") (pintype "passive"))
      (node (ref "C15") (pin "1") (pinfunction "1_1") (pintype "passive"))
      (node (ref "C16") (pin "1") (pinfunction "1_1") (pintype "passive"))
      (node (ref "C2") (pin "1") (pinfunction "1_1") (pintype "passive"))
      (node (ref "C22") (pin "1") (pinfunction "1_1") (pintype "passive"))
      (node (ref "C24") (pin "1") (pinfunction "1_1") (pintype "passive"))
      (node (ref "C25") (pin "1") (pinfunction "1_1") (pintype "passive"))
      (node (ref "C26") (pin "1") (pinfunction "1_1") (pintype "passive"))
      (node (ref "C31") (pin "1") (pinfunction "1_1") (pintype "passive"))
      (node (ref "C32") (pin "1") (pinfunction "1_1") (pintype "passive"))
      (node (ref "C33") (pin "1") (pinfunction "1_1") (pintype "passive"))
      (node (ref "C35") (pin "1") (pinfunction "1_1") (pintype "passive"))
      (node (ref "C36") (pin "1") (pinfunction "1_1") (pintype "passive"))
      (node (ref "C37") (pin "1") (pinfunction "1_1") (pintype "passive"))
      (node (ref "C38") (pin "1") (pinfunction "1_1") (pintype "passive"))
      (node (ref "C40") (pin "1") (pinfunction "1_1") (pintype "passive"))
      (node (ref "C41") (pin "1") (pinfunction "1_1") (pintype "passive"))
      (node (ref "C42") (pin "1") (pinfunction "1_1") (pintype "passive"))
      (node (ref "C43") (pin "1") (pinfunction "1_1") (pintype "passive"))
      (node (ref "C45") (pin "1") (pinfunction "1_1") (pintype "passive"))
      (node (ref "C47") (pin "1") (pinfunction "1_1") (pintype "passive"))
      (node (ref "C48") (pin "1") (pinfunction "1_1") (pintype "passive"))
      (node (ref "C49") (pin "1") (pinfunction "1_1") (pintype "passive"))
      (node (ref "C51") (pin "1") (pinfunction "1_1") (pintype "passive"))
      (node (ref "C58") (pin "1") (pinfunction "1_1") (pintype "passive"))
      (node (ref "C7") (pin "1") (pinfunction "1_1") (pintype "passive"))
      (node (ref "C9") (pin "1") (pinfunction "1_1") (pintype "passive"))
      (node (ref "FB1") (pin "1") (pinfunction "1_1") (pintype "passive"))
      (node (ref "FB2") (pin "1") (pinfunction "1_1") (pintype "passive"))
      (node (ref "JP2") (pin "1") (pinfunction "1_1") (pintype "passive"))
      (node (ref "JP3") (pin "1") (pinfunction "1_1") (pintype "passive"))
      (node (ref "L3") (pin "2") (pinfunction "2_2") (pintype "passive"))
      (node (ref "R1") (pin "2") (pinfunction "2_2") (pintype "passive"))
      (node (ref "R10") (pin "1") (pinfunction "1_1") (pintype "passive"))
      (node (ref "R13") (pin "2") (pinfunction "2_2") (pintype "passive"))
      (node (ref "R16") (pin "2") (pinfunction "2_2") (pintype "passive"))
      (node (ref "R18") (pin "2") (pinfunction "2_2") (pintype "passive"))
      (node (ref "R2") (pin "2") (pinfunction "2_2") (pintype "passive"))
      (node (ref "R20") (pin "2") (pinfunction "2_2") (pintype "passive"))
      (node (ref "R21") (pin "2") (pinfunction "2_2") (pintype "passive"))
      (node (ref "R26") (pin "2") (pinfunction "2_2") (pintype "passive"))
      (node (ref "R5") (pin "2") (pinfunction "2_2") (pintype "passive"))
      (node (ref "R6") (pin "2") (pinfunction "2_2") (pintype "passive"))
      (node (ref "R7") (pin "2") (pinfunction "2_2") (pintype "passive"))
      (node (ref "RN1") (pin "5") (pinfunction "5_5") (pintype "passive"))
      (node (ref "RN1") (pin "6") (pinfunction "6_6") (pintype "passive"))
      (node (ref "RN1") (pin "7") (pinfunction "7_7") (pintype "passive"))
      (node (ref "RN1") (pin "8") (pinfunction "8_8") (pintype "passive"))
      (node (ref "RN2") (pin "5") (pinfunction "5_5") (pintype "passive"))
      (node (ref "RN2") (pin "6") (pinfunction "6_6") (pintype "passive"))
      (node (ref "RN2") (pin "7") (pinfunction "7_7") (pintype "passive"))
      (node (ref "RN2") (pin "8") (pinfunction "8_8") (pintype "passive"))
      (node (ref "RN4") (pin "5") (pinfunction "5_5") (pintype "passive"))
      (node (ref "RN4") (pin "6") (pinfunction "6_6") (pintype "passive"))
      (node (ref "RN4") (pin "7") (pinfunction "7_7") (pintype "passive"))
      (node (ref "RN4") (pin "8") (pinfunction "8_8") (pintype "passive"))
      (node (ref "RN5") (pin "5") (pinfunction "5_5") (pintype "passive"))
      (node (ref "RN5") (pin "6") (pinfunction "6_6") (pintype "passive"))
      (node (ref "RN5") (pin "7") (pinfunction "7_7") (pintype "passive"))
      (node (ref "RN5") (pin "8") (pinfunction "8_8") (pintype "passive"))
      (node (ref "SV2") (pin "1") (pinfunction "1_1") (pintype "passive"))
      (node (ref "U10") (pin "24") (pinfunction "VCCA_24") (pintype "power_in"))
      (node (ref "U11") (pin "2") (pinfunction "3V3_2") (pintype "power_in"))
      (node (ref "U12") (pin "12") (pinfunction "EN2_12") (pintype "input"))
      (node (ref "U2") (pin "P103") (pinfunction "VCCO_1_P103") (pintype "input"))
      (node (ref "U2") (pin "P122") (pinfunction "VCCO_0_P122") (pintype "input"))
      (node (ref "U2") (pin "P125") (pinfunction "VCCO_0_P125") (pintype "input"))
      (node (ref "U2") (pin "P129") (pinfunction "VCCAUX_P129") (pintype "input"))
      (node (ref "U2") (pin "P135") (pinfunction "VCCO_0_P135") (pintype "input"))
      (node (ref "U2") (pin "P18") (pinfunction "VCCO_3_P18") (pintype "input"))
      (node (ref "U2") (pin "P20") (pinfunction "VCCAUX_P20") (pintype "input"))
      (node (ref "U2") (pin "P31") (pinfunction "VCCO_3_P31") (pintype "input"))
      (node (ref "U2") (pin "P36") (pinfunction "VCCAUX_P36") (pintype "input"))
      (node (ref "U2") (pin "P4") (pinfunction "VCCO_3_P4") (pintype "input"))
      (node (ref "U2") (pin "P42") (pinfunction "VCCO_2_P42") (pintype "input"))
      (node (ref "U2") (pin "P53") (pinfunction "VCCAUX_P53") (pintype "input"))
      (node (ref "U2") (pin "P63") (pinfunction "VCCO_2_P63") (pintype "input"))
      (node (ref "U2") (pin "P69") (pinfunction "IO_L1N_M0_CMPMISO_2_P69") (pintype "bidirectional"))
      (node (ref "U2") (pin "P76") (pinfunction "VCCO_1_P76") (pintype "input"))
      (node (ref "U2") (pin "P86") (pinfunction "VCCO_1_P86") (pintype "input"))
      (node (ref "U2") (pin "P90") (pinfunction "VCCAUX_P90") (pintype "input"))
      (node (ref "U3") (pin "6") (pinfunction "VCC_6") (pintype "power_in"))
      (node (ref "U4") (pin "20") (pinfunction "VCCIO_20") (pintype "power_in"))
      (node (ref "U4") (pin "31") (pinfunction "VCCIO_31") (pintype "power_in"))
      (node (ref "U4") (pin "42") (pinfunction "VCCIO_42") (pintype "power_in"))
      (node (ref "U4") (pin "50") (pinfunction "VREGIN_50") (pintype "input"))
      (node (ref "U4") (pin "56") (pinfunction "VCCIO_56") (pintype "power_in"))
      (node (ref "U5") (pin "24") (pinfunction "VCCA_24") (pintype "power_in"))
      (node (ref "U6") (pin "1") (pinfunction "EN_1") (pintype "bidirectional"))
      (node (ref "U6") (pin "4") (pinfunction "VCC_4") (pintype "bidirectional"))
      (node (ref "U7") (pin "1") (pinfunction "VCCA_1") (pintype "power_in"))
      (node (ref "U7") (pin "8") (pinfunction "OE_8") (pintype "input"))
      (node (ref "U8") (pin "24") (pinfunction "VCCA_24") (pintype "power_in"))
      (node (ref "U9") (pin "3") (pinfunction "W#_3") (pintype "input"))
      (node (ref "U9") (pin "7") (pinfunction "HOLD#_7") (pintype "input"))
      (node (ref "U9") (pin "8") (pinfunction "VCC_8") (pintype "power_in"))
    )
    (net (code "4") (name "+5V") (class "Default")
      (node (ref "C34") (pin "1") (pinfunction "1_1") (pintype "passive"))
      (node (ref "C39") (pin "1") (pinfunction "1_1") (pintype "passive"))
      (node (ref "C4") (pin "1") (pinfunction "1_1") (pintype "passive"))
      (node (ref "C44") (pin "1") (pinfunction "1_1") (pintype "passive"))
      (node (ref "C50") (pin "1") (pinfunction "1_1") (pintype "passive"))
      (node (ref "C54") (pin "1") (pinfunction "1_1") (pintype "passive"))
      (node (ref "C55") (pin "1") (pinfunction "1_1") (pintype "passive"))
      (node (ref "JP1") (pin "2") (pinfunction "2_2") (pintype "passive"))
      (node (ref "JP2") (pin "3") (pinfunction "3_3") (pintype "passive"))
      (node (ref "JP3") (pin "3") (pinfunction "3_3") (pintype "passive"))
      (node (ref "R4") (pin "2") (pinfunction "2_2") (pintype "passive"))
      (node (ref "U10") (pin "11") (pinfunction "VCC5V_11") (pintype "power_in"))
      (node (ref "U12") (pin "1") (pinfunction "VIN1_1") (pintype "power_in"))
      (node (ref "U12") (pin "16") (pinfunction "VIN2_16") (pintype "power_in"))
      (node (ref "U12") (pin "5") (pinfunction "EN1_5") (pintype "input"))
      (node (ref "U5") (pin "11") (pinfunction "VCC5V_11") (pintype "power_in"))
      (node (ref "U7") (pin "14") (pinfunction "VCCB_14") (pintype "power_in"))
      (node (ref "U8") (pin "11") (pinfunction "VCC5V_11") (pintype "power_in"))
    )
    (net (code "5") (name "5V_SUP") (class "Default")
      (node (ref "C3") (pin "1") (pinfunction "1_1") (pintype "passive"))
      (node (ref "D1") (pin "C") (pinfunction "C_C") (pintype "passive"))
      (node (ref "J1") (pin "CENTER") (pinfunction "CENTER_CENTER") (pintype "power_in"))
      (node (ref "JP1") (pin "1") (pinfunction "1_1") (pintype "passive"))
      (node (ref "SV1") (pin "1") (pinfunction "1_1") (pintype "passive"))
      (node (ref "SV3") (pin "1") (pinfunction "1_1") (pintype "passive"))
      (node (ref "SV4") (pin "1") (pinfunction "1_1") (pintype "passive"))
    )
    (net (code "6") (name "ESP_CTS") (class "Default")
      (node (ref "U11") (pin "22") (pinfunction "SDI/SD1_22") (pintype "bidirectional"))
      (node (ref "U2") (pin "P1") (pinfunction "IO_L83N_VREF_3_P1") (pintype "bidirectional"))
    )
    (net (code "7") (name "ESP_EN") (class "Default")
      (node (ref "R1") (pin "1") (pinfunction "1_1") (pintype "passive"))
      (node (ref "U11") (pin "3") (pinfunction "EN_3") (pintype "input"))
      (node (ref "U2") (pin "P8") (pinfunction "IO_L51P_3_P8") (pintype "bidirectional"))
    )
    (net (code "8") (name "ESP_IO0") (class "Default")
      (node (ref "R2") (pin "1") (pinfunction "1_1") (pintype "passive"))
      (node (ref "U11") (pin "25") (pinfunction "IO0_25") (pintype "bidirectional"))
      (node (ref "U2") (pin "P5") (pinfunction "IO_L52N_3_P5") (pintype "bidirectional"))
    )
    (net (code "9") (name "ESP_RTS") (class "Default")
      (node (ref "U11") (pin "21") (pinfunction "SDO/SD0_21") (pintype "bidirectional"))
      (node (ref "U2") (pin "P2") (pinfunction "IO_L83P_3_P2") (pintype "bidirectional"))
    )
    (net (code "10") (name "ESP_RX") (class "Default")
      (node (ref "U11") (pin "27") (pinfunction "IO16_27") (pintype "bidirectional"))
      (node (ref "U2") (pin "P6") (pinfunction "IO_L52P_3_P6") (pintype "bidirectional"))
    )
    (net (code "11") (name "ESP_TDO") (class "Default")
      (node (ref "SV2") (pin "4") (pinfunction "4_4") (pintype "passive"))
      (node (ref "U11") (pin "23") (pinfunction "IO15_23") (pintype "bidirectional"))
      (node (ref "U4") (pin "18") (pinfunction "ADBUS2_18") (pintype "bidirectional"))
    )
    (net (code "12") (name "ESP_TX") (class "Default")
      (node (ref "U11") (pin "28") (pinfunction "IO17_28") (pintype "bidirectional"))
      (node (ref "U2") (pin "P7") (pinfunction "IO_L51N_3_P7") (pintype "bidirectional"))
    )
    (net (code "13") (name "FPGA_CLK20") (class "Default")
      (node (ref "U2") (pin "P87") (pinfunction "IO_L42N_GCLK6_TRDY1_1_P87") (pintype "bidirectional"))
      (node (ref "U6") (pin "3") (pinfunction "OUT_3") (pintype "bidirectional"))
    )
    (net (code "14") (name "FPGA_TDO") (class "Default")
      (node (ref "U11") (pin "14") (pinfunction "IO12_14") (pintype "bidirectional"))
      (node (ref "U2") (pin "P106") (pinfunction "TDO_P106") (pintype "output"))
    )
    (net (code "15") (name "GND") (class "Default")
      (node (ref "C1") (pin "2") (pinfunction "2_2") (pintype "passive"))
      (node (ref "C10") (pin "2") (pinfunction "2_2") (pintype "passive"))
      (node (ref "C11") (pin "2") (pinfunction "2_2") (pintype "passive"))
      (node (ref "C12") (pin "2") (pinfunction "2_2") (pintype "passive"))
      (node (ref "C13") (pin "2") (pinfunction "2_2") (pintype "passive"))
      (node (ref "C14") (pin "2") (pinfunction "2_2") (pintype "passive"))
      (node (ref "C15") (pin "2") (pinfunction "2_2") (pintype "passive"))
      (node (ref "C16") (pin "2") (pinfunction "2_2") (pintype "passive"))
      (node (ref "C17") (pin "2") (pinfunction "2_2") (pintype "passive"))
      (node (ref "C18") (pin "2") (pinfunction "2_2") (pintype "passive"))
      (node (ref "C19") (pin "2") (pinfunction "2_2") (pintype "passive"))
      (node (ref "C2") (pin "2") (pinfunction "2_2") (pintype "passive"))
      (node (ref "C20") (pin "2") (pinfunction "2_2") (pintype "passive"))
      (node (ref "C21") (pin "2") (pinfunction "2_2") (pintype "passive"))
      (node (ref "C22") (pin "2") (pinfunction "2_2") (pintype "passive"))
      (node (ref "C23") (pin "2") (pinfunction "2_2") (pintype "passive"))
      (node (ref "C24") (pin "2") (pinfunction "2_2") (pintype "passive"))
      (node (ref "C25") (pin "2") (pinfunction "2_2") (pintype "passive"))
      (node (ref "C26") (pin "2") (pinfunction "2_2") (pintype "passive"))
      (node (ref "C27") (pin "2") (pinfunction "2_2") (pintype "passive"))
      (node (ref "C28") (pin "2") (pinfunction "2_2") (pintype "passive"))
      (node (ref "C29") (pin "2") (pinfunction "2_2") (pintype "passive"))
      (node (ref "C3") (pin "2") (pinfunction "2_2") (pintype "passive"))
      (node (ref "C30") (pin "2") (pinfunction "2_2") (pintype "passive"))
      (node (ref "C31") (pin "2") (pinfunction "2_2") (pintype "passive"))
      (node (ref "C32") (pin "2") (pinfunction "2_2") (pintype "passive"))
      (node (ref "C33") (pin "2") (pinfunction "2_2") (pintype "passive"))
      (node (ref "C34") (pin "2") (pinfunction "2_2") (pintype "passive"))
      (node (ref "C35") (pin "2") (pinfunction "2_2") (pintype "passive"))
      (node (ref "C36") (pin "2") (pinfunction "2_2") (pintype "passive"))
      (node (ref "C37") (pin "2") (pinfunction "2_2") (pintype "passive"))
      (node (ref "C38") (pin "2") (pinfunction "2_2") (pintype "passive"))
      (node (ref "C39") (pin "2") (pinfunction "2_2") (pintype "passive"))
      (node (ref "C4") (pin "2") (pinfunction "2_2") (pintype "passive"))
      (node (ref "C40") (pin "2") (pinfunction "2_2") (pintype "passive"))
      (node (ref "C41") (pin "2") (pinfunction "2_2") (pintype "passive"))
      (node (ref "C42") (pin "2") (pinfunction "2_2") (pintype "passive"))
      (node (ref "C43") (pin "2") (pinfunction "2_2") (pintype "passive"))
      (node (ref "C44") (pin "2") (pinfunction "2_2") (pintype "passive"))
      (node (ref "C45") (pin "2") (pinfunction "2_2") (pintype "passive"))
      (node (ref "C46") (pin "2") (pinfunction "2_2") (pintype "passive"))
      (node (ref "C47") (pin "2") (pinfunction "2_2") (pintype "passive"))
      (node (ref "C48") (pin "2") (pinfunction "2_2") (pintype "passive"))
      (node (ref "C49") (pin "2") (pinfunction "2_2") (pintype "passive"))
      (node (ref "C50") (pin "2") (pinfunction "2_2") (pintype "passive"))
      (node (ref "C51") (pin "2") (pinfunction "2_2") (pintype "passive"))
      (node (ref "C54") (pin "2") (pinfunction "2_2") (pintype "passive"))
      (node (ref "C55") (pin "2") (pinfunction "2_2") (pintype "passive"))
      (node (ref "C56") (pin "2") (pinfunction "2_2") (pintype "passive"))
      (node (ref "C58") (pin "2") (pinfunction "2_2") (pintype "passive"))
      (node (ref "C60") (pin "2") (pinfunction "2_2") (pintype "passive"))
      (node (ref "C7") (pin "2") (pinfunction "2_2") (pintype "passive"))
      (node (ref "C8") (pin "2") (pinfunction "2_2") (pintype "passive"))
      (node (ref "C9") (pin "2") (pinfunction "2_2") (pintype "passive"))
      (node (ref "D1") (pin "A") (pinfunction "A_A") (pintype "passive"))
      (node (ref "J1") (pin "BARREL") (pinfunction "BARREL_BARREL") (pintype "power_in"))
      (node (ref "LED1") (pin "C") (pinfunction "C_C") (pintype "passive"))
      (node (ref "R11") (pin "2") (pinfunction "2_2") (pintype "passive"))
      (node (ref "R14") (pin "1") (pinfunction "1_1") (pintype "passive"))
      (node (ref "R17") (pin "1") (pinfunction "1_1") (pintype "passive"))
      (node (ref "R19") (pin "1") (pinfunction "1_1") (pintype "passive"))
      (node (ref "R22") (pin "1") (pinfunction "1_1") (pintype "passive"))
      (node (ref "R27") (pin "2") (pinfunction "2_2") (pintype "passive"))
      (node (ref "R29") (pin "2") (pinfunction "2_2") (pintype "passive"))
      (node (ref "R9") (pin "1") (pinfunction "1_1") (pintype "passive"))
      (node (ref "RN3") (pin "1") (pinfunction "1_1") (pintype "passive"))
      (node (ref "RN3") (pin "2") (pinfunction "2_2") (pintype "passive"))
      (node (ref "RN3") (pin "3") (pinfunction "3_3") (pintype "passive"))
      (node (ref "RN3") (pin "4") (pinfunction "4_4") (pintype "passive"))
      (node (ref "SV1") (pin "2") (pinfunction "2_2") (pintype "passive"))
      (node (ref "SV2") (pin "2") (pinfunction "2_2") (pintype "passive"))
      (node (ref "SV3") (pin "4") (pinfunction "4_4") (pintype "passive"))
      (node (ref "SV4") (pin "4") (pinfunction "4_4") (pintype "passive"))
      (node (ref "U10") (pin "14") (pinfunction "GND_14") (pintype "power_in"))
      (node (ref "U10") (pin "19") (pinfunction "GND_19") (pintype "power_in"))
      (node (ref "U10") (pin "6") (pinfunction "GND_6") (pintype "power_in"))
      (node (ref "U11") (pin "1") (pinfunction "GND_1") (pintype "power_in"))
      (node (ref "U11") (pin "15") (pinfunction "GND_15") (pintype "power_in"))
      (node (ref "U11") (pin "38") (pinfunction "GND_38") (pintype "power_in"))
      (node (ref "U11") (pin "PAD") (pinfunction "GND_PAD") (pintype "power_in"))
      (node (ref "U12") (pin "13") (pinfunction "PGND2_13") (pintype "power_in"))
      (node (ref "U12") (pin "4") (pinfunction "PGND1_4") (pintype "power_in"))
      (node (ref "U12") (pin "8") (pinfunction "GND_8") (pintype "power_in"))
      (node (ref "U2") (pin "P108") (pinfunction "GND_P108") (pintype "power_in"))
      (node (ref "U2") (pin "P113") (pinfunction "GND_P113") (pintype "power_in"))
      (node (ref "U2") (pin "P13") (pinfunction "GND_P13") (pintype "power_in"))
      (node (ref "U2") (pin "P130") (pinfunction "GND_P130") (pintype "power_in"))
      (node (ref "U2") (pin "P136") (pinfunction "GND_P136") (pintype "power_in"))
      (node (ref "U2") (pin "P25") (pinfunction "GND_P25") (pintype "power_in"))
      (node (ref "U2") (pin "P3") (pinfunction "GND_P3") (pintype "power_in"))
      (node (ref "U2") (pin "P49") (pinfunction "GND_P49") (pintype "power_in"))
      (node (ref "U2") (pin "P54") (pinfunction "GND_P54") (pintype "power_in"))
      (node (ref "U2") (pin "P60") (pinfunction "IO_L13P_M1_2_P60") (pintype "bidirectional"))
      (node (ref "U2") (pin "P68") (pinfunction "GND_P68") (pintype "power_in"))
      (node (ref "U2") (pin "P73") (pinfunction "SUSPEND_P73") (pintype "input"))
      (node (ref "U2") (pin "P77") (pinfunction "GND_P77") (pintype "power_in"))
      (node (ref "U2") (pin "P91") (pinfunction "GND_P91") (pintype "power_in"))
      (node (ref "U2") (pin "P96") (pinfunction "GND_P96") (pintype "power_in"))
      (node (ref "U3") (pin "2") (pinfunction "VSS_2") (pintype "power_in"))
      (node (ref "U4") (pin "1") (pinfunction "GND_1") (pintype "power_in"))
      (node (ref "U4") (pin "10") (pinfunction "AGND_10") (pintype "power_in"))
      (node (ref "U4") (pin "11") (pinfunction "GND_11") (pintype "power_in"))
      (node (ref "U4") (pin "13") (pinfunction "TEST_13") (pintype "input"))
      (node (ref "U4") (pin "15") (pinfunction "GND_15") (pintype "power_in"))
      (node (ref "U4") (pin "25") (pinfunction "GND_25") (pintype "power_in"))
      (node (ref "U4") (pin "35") (pinfunction "GND_35") (pintype "power_in"))
      (node (ref "U4") (pin "47") (pinfunction "GND_47") (pintype "power_in"))
      (node (ref "U4") (pin "5") (pinfunction "GND_5") (pintype "power_in"))
      (node (ref "U4") (pin "51") (pinfunction "GND_51") (pintype "power_in"))
      (node (ref "U5") (pin "14") (pinfunction "GND_14") (pintype "power_in"))
      (node (ref "U5") (pin "19") (pinfunction "GND_19") (pintype "power_in"))
      (node (ref "U5") (pin "6") (pinfunction "GND_6") (pintype "power_in"))
      (node (ref "U6") (pin "2") (pinfunction "GND_2") (pintype "bidirectional"))
      (node (ref "U7") (pin "7") (pinfunction "GND_7") (pintype "power_in"))
      (node (ref "U8") (pin "14") (pinfunction "GND_14") (pintype "power_in"))
      (node (ref "U8") (pin "19") (pinfunction "GND_19") (pintype "power_in"))
      (node (ref "U8") (pin "6") (pinfunction "GND_6") (pintype "power_in"))
      (node (ref "U9") (pin "4") (pinfunction "VSS_4") (pintype "power_in"))
      (node (ref "X1") (pin "GND") (pinfunction "GND_GND") (pintype "bidirectional"))
      (node (ref "X2") (pin "11") (pinfunction "TMDS_CLK_SHIELD_11") (pintype "power_in"))
      (node (ref "X2") (pin "14") (pinfunction "RESERVED/HEAC_P_14") (pintype "bidirectional"))
      (node (ref "X2") (pin "17") (pinfunction "DDC/CDC/HEAC_GND_17") (pintype "power_in"))
      (node (ref "X2") (pin "2") (pinfunction "TMDS_DATA2_SHIELD_2") (pintype "power_in"))
      (node (ref "X2") (pin "5") (pinfunction "TMDS_DATA1_SHIELD_5") (pintype "power_in"))
      (node (ref "X2") (pin "8") (pinfunction "TMDS_DATA0_SHIELD_8") (pintype "power_in"))
      (node (ref "X3") (pin "11") (pinfunction "TMDS_CLK_SHIELD_11") (pintype "power_in"))
      (node (ref "X3") (pin "14") (pinfunction "RESERVED/HEAC_P_14") (pintype "bidirectional"))
      (node (ref "X3") (pin "17") (pinfunction "DDC/CDC/HEAC_GND_17") (pintype "power_in"))
      (node (ref "X3") (pin "2") (pinfunction "TMDS_DATA2_SHIELD_2") (pintype "power_in"))
      (node (ref "X3") (pin "5") (pinfunction "TMDS_DATA1_SHIELD_5") (pintype "power_in"))
      (node (ref "X3") (pin "8") (pinfunction "TMDS_DATA0_SHIELD_8") (pintype "power_in"))
      (node (ref "X4") (pin "11") (pinfunction "TMDS_CLK_SHIELD_11") (pintype "power_in"))
      (node (ref "X4") (pin "14") (pinfunction "RESERVED/HEAC_P_14") (pintype "bidirectional"))
      (node (ref "X4") (pin "17") (pinfunction "DDC/CDC/HEAC_GND_17") (pintype "power_in"))
      (node (ref "X4") (pin "2") (pinfunction "TMDS_DATA2_SHIELD_2") (pintype "power_in"))
      (node (ref "X4") (pin "5") (pinfunction "TMDS_DATA1_SHIELD_5") (pintype "power_in"))
      (node (ref "X4") (pin "8") (pinfunction "TMDS_DATA0_SHIELD_8") (pintype "power_in"))
      (node (ref "X5") (pin "11") (pinfunction "11_11") (pintype "passive"))
      (node (ref "X5") (pin "5") (pinfunction "5_5") (pintype "passive"))
      (node (ref "X6") (pin "11") (pinfunction "11_11") (pintype "passive"))
      (node (ref "X6") (pin "5") (pinfunction "5_5") (pintype "passive"))
      (node (ref "Y1") (pin "2") (pinfunction "GND_2") (pintype "power_in"))
      (node (ref "Y1") (pin "4") (pinfunction "GND_4") (pintype "power_in"))
    )
    (net (code "16") (name "HDMI_RX0_CEC") (class "Default")
      (node (ref "U5") (pin "7") (pinfunction "CEC_B_7") (pintype "input"))
      (node (ref "X2") (pin "13") (pinfunction "CEC_13") (pintype "bidirectional"))
    )
    (net (code "17") (name "HDMI_RX0_CEC_3V3") (class "Default")
      (node (ref "U2") (pin "P127") (pinfunction "IO_L36P_GCLK15_0_P127") (pintype "bidirectional"))
      (node (ref "U5") (pin "1") (pinfunction "CEC_A_1") (pintype "output"))
    )
    (net (code "18") (name "HDMI_RX0_CLK_N") (class "Default")
      (node (ref "RN2") (pin "4") (pinfunction "4_4") (pintype "passive"))
      (node (ref "U2") (pin "P133") (pinfunction "IO_L34N_GCLK18_0_P133") (pintype "bidirectional"))
      (node (ref "U5") (pin "15") (pinfunction "CLK-_15") (pintype "input"))
      (node (ref "X2") (pin "12") (pinfunction "TMDS_CLK_N_12") (pintype "bidirectional"))
    )
    (net (code "19") (name "HDMI_RX0_CLK_P") (class "Default")
      (node (ref "RN2") (pin "3") (pinfunction "3_3") (pintype "passive"))
      (node (ref "U2") (pin "P134") (pinfunction "IO_L34P_GCLK19_0_P134") (pintype "bidirectional"))
      (node (ref "U5") (pin "16") (pinfunction "CLK+_16") (pintype "input"))
      (node (ref "X2") (pin "10") (pinfunction "TMDS_CLK_P_10") (pintype "bidirectional"))
    )
    (net (code "20") (name "HDMI_RX0_DATA0_N") (class "Default")
      (node (ref "RN2") (pin "2") (pinfunction "2_2") (pintype "passive"))
      (node (ref "U2") (pin "P137") (pinfunction "IO_L4N_0_P137") (pintype "bidirectional"))
      (node (ref "U5") (pin "17") (pinfunction "D0-_17") (pintype "input"))
      (node (ref "X2") (pin "9") (pinfunction "TMDS_DATA0_N_9") (pintype "bidirectional"))
    )
    (net (code "21") (name "HDMI_RX0_DATA0_P") (class "Default")
      (node (ref "RN2") (pin "1") (pinfunction "1_1") (pintype "passive"))
      (node (ref "U2") (pin "P138") (pinfunction "IO_L4P_0_P138") (pintype "bidirectional"))
      (node (ref "U5") (pin "18") (pinfunction "D0+_18") (pintype "input"))
      (node (ref "X2") (pin "7") (pinfunction "TMDS_DATA0_P_7") (pintype "bidirectional"))
    )
    (net (code "22") (name "HDMI_RX0_DATA1_N") (class "Default")
      (node (ref "RN1") (pin "4") (pinfunction "4_4") (pintype "passive"))
      (node (ref "U2") (pin "P139") (pinfunction "IO_L3N_0_P139") (pintype "bidirectional"))
      (node (ref "U5") (pin "20") (pinfunction "D1-_20") (pintype "input"))
      (node (ref "X2") (pin "6") (pinfunction "TMDS_DATA1_N_6") (pintype "bidirectional"))
    )
    (net (code "23") (name "HDMI_RX0_DATA1_P") (class "Default")
      (node (ref "RN1") (pin "3") (pinfunction "3_3") (pintype "passive"))
      (node (ref "U2") (pin "P140") (pinfunction "IO_L3P_0_P140") (pintype "bidirectional"))
      (node (ref "U5") (pin "21") (pinfunction "D1+_21") (pintype "input"))
      (node (ref "X2") (pin "4") (pinfunction "TMDS_DATA1_P_4") (pintype "bidirectional"))
    )
    (net (code "24") (name "HDMI_RX0_DATA2_N") (class "Default")
      (node (ref "RN1") (pin "2") (pinfunction "2_2") (pintype "passive"))
      (node (ref "U2") (pin "P141") (pinfunction "IO_L2N_0_P141") (pintype "bidirectional"))
      (node (ref "U5") (pin "22") (pinfunction "D2-_22") (pintype "input"))
      (node (ref "X2") (pin "3") (pinfunction "TMDS_DATA2_N_3") (pintype "bidirectional"))
    )
    (net (code "25") (name "HDMI_RX0_DATA2_P") (class "Default")
      (node (ref "RN1") (pin "1") (pinfunction "1_1") (pintype "passive"))
      (node (ref "U2") (pin "P142") (pinfunction "IO_L2P_0_P142") (pintype "bidirectional"))
      (node (ref "U5") (pin "23") (pinfunction "D2+_23") (pintype "input"))
      (node (ref "X2") (pin "1") (pinfunction "TMDS_DATA2_P_1") (pintype "bidirectional"))
    )
    (net (code "26") (name "HDMI_RX0_EN") (class "Default")
      (node (ref "R14") (pin "2") (pinfunction "2_2") (pintype "passive"))
      (node (ref "U2") (pin "P123") (pinfunction "IO_L37N_GCLK12_0_P123") (pintype "bidirectional"))
      (node (ref "U5") (pin "12") (pinfunction "CT_HPD_12") (pintype "input"))
      (node (ref "U5") (pin "5") (pinfunction "LS_OE_5") (pintype "input"))
    )
    (net (code "27") (name "HDMI_RX0_HPD") (class "Default")
      (node (ref "U5") (pin "10") (pinfunction "HPD_B_10") (pintype "input"))
      (node (ref "X2") (pin "18") (pinfunction "+5V_SUPPLY_18") (pintype "bidirectional"))
    )
    (net (code "28") (name "HDMI_RX0_HPD_3V3") (class "Default")
      (node (ref "U2") (pin "P121") (pinfunction "IO_L62P_0_P121") (pintype "bidirectional"))
      (node (ref "U5") (pin "4") (pinfunction "HPD_A_4") (pintype "output"))
    )
    (net (code "29") (name "HDMI_RX0_SCL") (class "Default")
      (node (ref "U5") (pin "8") (pinfunction "SCL_B_8") (pintype "input"))
      (node (ref "X2") (pin "15") (pinfunction "SCL_15") (pintype "bidirectional"))
    )
    (net (code "30") (name "HDMI_RX0_SCL_3V3") (class "Default")
      (node (ref "U2") (pin "P126") (pinfunction "IO_L36N_GCLK14_0_P126") (pintype "bidirectional"))
      (node (ref "U5") (pin "2") (pinfunction "SCL_A_2") (pintype "output"))
    )
    (net (code "31") (name "HDMI_RX0_SDA") (class "Default")
      (node (ref "U5") (pin "9") (pinfunction "SDA_B_9") (pintype "input"))
      (node (ref "X2") (pin "16") (pinfunction "SDA_16") (pintype "bidirectional"))
    )
    (net (code "32") (name "HDMI_RX0_SDA_3V3") (class "Default")
      (node (ref "U2") (pin "P124") (pinfunction "IO_L37P_GCLK13_0_P124") (pintype "bidirectional"))
      (node (ref "U5") (pin "3") (pinfunction "SDA_A_3") (pintype "output"))
    )
    (net (code "33") (name "HDMI_RX1_5V") (class "Default")
      (node (ref "R23") (pin "1") (pinfunction "1_1") (pintype "passive"))
      (node (ref "U10") (pin "13") (pinfunction "5V_OUT_13") (pintype "power_in"))
    )
    (net (code "34") (name "HDMI_RX1_CEC") (class "Default")
      (node (ref "U10") (pin "7") (pinfunction "CEC_B_7") (pintype "input"))
      (node (ref "X4") (pin "13") (pinfunction "CEC_13") (pintype "bidirectional"))
    )
    (net (code "35") (name "HDMI_RX1_CEC_3V3") (class "Default")
      (node (ref "U10") (pin "1") (pinfunction "CEC_A_1") (pintype "output"))
      (node (ref "U2") (pin "P17") (pinfunction "IO_L43P_GCLK23_3_P17") (pintype "bidirectional"))
    )
    (net (code "36") (name "HDMI_RX1_CLK_N") (class "Default")
      (node (ref "RN5") (pin "4") (pinfunction "4_4") (pintype "passive"))
      (node (ref "U10") (pin "15") (pinfunction "CLK-_15") (pintype "input"))
      (node (ref "U2") (pin "P23") (pinfunction "IO_L41N_GCLK26_3_P23") (pintype "bidirectional"))
      (node (ref "X4") (pin "12") (pinfunction "TMDS_CLK_N_12") (pintype "bidirectional"))
    )
    (net (code "37") (name "HDMI_RX1_CLK_P") (class "Default")
      (node (ref "RN5") (pin "3") (pinfunction "3_3") (pintype "passive"))
      (node (ref "U10") (pin "16") (pinfunction "CLK+_16") (pintype "input"))
      (node (ref "U2") (pin "P24") (pinfunction "IO_L41P_GCLK27_3_P24") (pintype "bidirectional"))
      (node (ref "X4") (pin "10") (pinfunction "TMDS_CLK_P_10") (pintype "bidirectional"))
    )
    (net (code "38") (name "HDMI_RX1_DATA0_N") (class "Default")
      (node (ref "RN5") (pin "2") (pinfunction "2_2") (pintype "passive"))
      (node (ref "U10") (pin "17") (pinfunction "D0-_17") (pintype "input"))
      (node (ref "U2") (pin "P26") (pinfunction "IO_L37N_3_P26") (pintype "bidirectional"))
      (node (ref "X4") (pin "9") (pinfunction "TMDS_DATA0_N_9") (pintype "bidirectional"))
    )
    (net (code "39") (name "HDMI_RX1_DATA0_P") (class "Default")
      (node (ref "RN5") (pin "1") (pinfunction "1_1") (pintype "passive"))
      (node (ref "U10") (pin "18") (pinfunction "D0+_18") (pintype "input"))
      (node (ref "U2") (pin "P27") (pinfunction "IO_L37P_3_P27") (pintype "bidirectional"))
      (node (ref "X4") (pin "7") (pinfunction "TMDS_DATA0_P_7") (pintype "bidirectional"))
    )
    (net (code "40") (name "HDMI_RX1_DATA1_N") (class "Default")
      (node (ref "RN4") (pin "4") (pinfunction "4_4") (pintype "passive"))
      (node (ref "U10") (pin "20") (pinfunction "D1-_20") (pintype "input"))
      (node (ref "U2") (pin "P29") (pinfunction "IO_L36N_3_P29") (pintype "bidirectional"))
      (node (ref "X4") (pin "6") (pinfunction "TMDS_DATA1_N_6") (pintype "bidirectional"))
    )
    (net (code "41") (name "HDMI_RX1_DATA1_P") (class "Default")
      (node (ref "RN4") (pin "3") (pinfunction "3_3") (pintype "passive"))
      (node (ref "U10") (pin "21") (pinfunction "D1+_21") (pintype "input"))
      (node (ref "U2") (pin "P30") (pinfunction "IO_L36P_3_P30") (pintype "bidirectional"))
      (node (ref "X4") (pin "4") (pinfunction "TMDS_DATA1_P_4") (pintype "bidirectional"))
    )
    (net (code "42") (name "HDMI_RX1_DATA2_N") (class "Default")
      (node (ref "RN4") (pin "2") (pinfunction "2_2") (pintype "passive"))
      (node (ref "U10") (pin "22") (pinfunction "D2-_22") (pintype "input"))
      (node (ref "U2") (pin "P32") (pinfunction "IO_L2N_3_P32") (pintype "bidirectional"))
      (node (ref "X4") (pin "3") (pinfunction "TMDS_DATA2_N_3") (pintype "bidirectional"))
    )
    (net (code "43") (name "HDMI_RX1_DATA2_P") (class "Default")
      (node (ref "RN4") (pin "1") (pinfunction "1_1") (pintype "passive"))
      (node (ref "U10") (pin "23") (pinfunction "D2+_23") (pintype "input"))
      (node (ref "U2") (pin "P33") (pinfunction "IO_L2P_3_P33") (pintype "bidirectional"))
      (node (ref "X4") (pin "1") (pinfunction "TMDS_DATA2_P_1") (pintype "bidirectional"))
    )
    (net (code "44") (name "HDMI_RX1_EN") (class "Default")
      (node (ref "R22") (pin "2") (pinfunction "2_2") (pintype "passive"))
      (node (ref "U10") (pin "12") (pinfunction "CT_HPD_12") (pintype "input"))
      (node (ref "U10") (pin "5") (pinfunction "LS_OE_5") (pintype "input"))
      (node (ref "U2") (pin "P14") (pinfunction "IO_L44N_GCLK20_3_P14") (pintype "bidirectional"))
    )
    (net (code "45") (name "HDMI_RX1_HPD") (class "Default")
      (node (ref "U10") (pin "10") (pinfunction "HPD_B_10") (pintype "input"))
      (node (ref "X4") (pin "18") (pinfunction "+5V_SUPPLY_18") (pintype "bidirectional"))
    )
    (net (code "46") (name "HDMI_RX1_HPD_3V3") (class "Default")
      (node (ref "U10") (pin "4") (pinfunction "HPD_A_4") (pintype "output"))
      (node (ref "U2") (pin "P12") (pinfunction "IO_L49P_3_P12") (pintype "bidirectional"))
    )
    (net (code "47") (name "HDMI_RX1_SCL") (class "Default")
      (node (ref "U10") (pin "8") (pinfunction "SCL_B_8") (pintype "input"))
      (node (ref "X4") (pin "15") (pinfunction "SCL_15") (pintype "bidirectional"))
    )
    (net (code "48") (name "HDMI_RX1_SCL_3V3") (class "Default")
      (node (ref "U10") (pin "2") (pinfunction "SCL_A_2") (pintype "output"))
      (node (ref "U2") (pin "P16") (pinfunction "IO_L43N_GCLK22_IRDY2_3_P16") (pintype "bidirectional"))
    )
    (net (code "49") (name "HDMI_RX1_SDA") (class "Default")
      (node (ref "U10") (pin "9") (pinfunction "SDA_B_9") (pintype "input"))
      (node (ref "X4") (pin "16") (pinfunction "SDA_16") (pintype "bidirectional"))
    )
    (net (code "50") (name "HDMI_RX1_SDA_3V3") (class "Default")
      (node (ref "U10") (pin "3") (pinfunction "SDA_A_3") (pintype "output"))
      (node (ref "U2") (pin "P15") (pinfunction "IO_L44P_GCLK21_3_P15") (pintype "bidirectional"))
    )
    (net (code "51") (name "HDMI_RX_5V") (class "Default")
      (node (ref "R15") (pin "1") (pinfunction "1_1") (pintype "passive"))
      (node (ref "U5") (pin "13") (pinfunction "5V_OUT_13") (pintype "power_in"))
    )
    (net (code "52") (name "HDMI_TX_5V") (class "Default")
      (node (ref "C46") (pin "1") (pinfunction "1_1") (pintype "passive"))
      (node (ref "U8") (pin "13") (pinfunction "5V_OUT_13") (pintype "power_in"))
      (node (ref "X3") (pin "18") (pinfunction "+5V_SUPPLY_18") (pintype "bidirectional"))
    )
    (net (code "53") (name "HDMI_TX_CEC") (class "Default")
      (node (ref "U8") (pin "7") (pinfunction "CEC_B_7") (pintype "input"))
      (node (ref "X3") (pin "13") (pinfunction "CEC_13") (pintype "bidirectional"))
    )
    (net (code "54") (name "HDMI_TX_CEC_3V3") (class "Default")
      (node (ref "U2") (pin "P47") (pinfunction "IO_L48N_RDWR_B_VREF_2_P47") (pintype "bidirectional"))
      (node (ref "U8") (pin "1") (pinfunction "CEC_A_1") (pintype "output"))
    )
    (net (code "55") (name "HDMI_TX_CLK_N") (class "Default")
      (node (ref "U2") (pin "P50") (pinfunction "IO_L31N_GCLK30_D15_2_P50") (pintype "bidirectional"))
      (node (ref "U8") (pin "15") (pinfunction "CLK-_15") (pintype "input"))
      (node (ref "X3") (pin "12") (pinfunction "TMDS_CLK_N_12") (pintype "bidirectional"))
    )
    (net (code "56") (name "HDMI_TX_CLK_P") (class "Default")
      (node (ref "U2") (pin "P51") (pinfunction "IO_L31P_GCLK31_D14_2_P51") (pintype "bidirectional"))
      (node (ref "U8") (pin "16") (pinfunction "CLK+_16") (pintype "input"))
      (node (ref "X3") (pin "10") (pinfunction "TMDS_CLK_P_10") (pintype "bidirectional"))
    )
    (net (code "57") (name "HDMI_TX_CTRL_EN") (class "Default")
      (node (ref "R17") (pin "2") (pinfunction "2_2") (pintype "passive"))
      (node (ref "U2") (pin "P44") (pinfunction "IO_L62P_D5_2_P44") (pintype "bidirectional"))
      (node (ref "U8") (pin "12") (pinfunction "CT_HPD_12") (pintype "input"))
      (node (ref "U8") (pin "5") (pinfunction "LS_OE_5") (pintype "input"))
    )
    (net (code "58") (name "HDMI_TX_DATA0_N") (class "Default")
      (node (ref "U2") (pin "P55") (pinfunction "IO_L30N_GCLK0_USERCCLK_2_P55") (pintype "bidirectional"))
      (node (ref "U8") (pin "17") (pinfunction "D0-_17") (pintype "input"))
      (node (ref "X3") (pin "9") (pinfunction "TMDS_DATA0_N_9") (pintype "bidirectional"))
    )
    (net (code "59") (name "HDMI_TX_DATA0_P") (class "Default")
      (node (ref "U2") (pin "P56") (pinfunction "IO_L30P_GCLK1_D13_2_P56") (pintype "bidirectional"))
      (node (ref "U8") (pin "18") (pinfunction "D0+_18") (pintype "input"))
      (node (ref "X3") (pin "7") (pinfunction "TMDS_DATA0_P_7") (pintype "bidirectional"))
    )
    (net (code "60") (name "HDMI_TX_DATA1_N") (class "Default")
      (node (ref "U2") (pin "P57") (pinfunction "IO_L14N_D12_2_P57") (pintype "bidirectional"))
      (node (ref "U8") (pin "20") (pinfunction "D1-_20") (pintype "input"))
      (node (ref "X3") (pin "6") (pinfunction "TMDS_DATA1_N_6") (pintype "bidirectional"))
    )
    (net (code "61") (name "HDMI_TX_DATA1_P") (class "Default")
      (node (ref "U2") (pin "P58") (pinfunction "IO_L14P_D11_2_P58") (pintype "bidirectional"))
      (node (ref "U8") (pin "21") (pinfunction "D1+_21") (pintype "input"))
      (node (ref "X3") (pin "4") (pinfunction "TMDS_DATA1_P_4") (pintype "bidirectional"))
    )
    (net (code "62") (name "HDMI_TX_DATA2_N") (class "Default")
      (node (ref "U2") (pin "P61") (pinfunction "IO_L12N_D2_MISO3_2_P61") (pintype "bidirectional"))
      (node (ref "U8") (pin "22") (pinfunction "D2-_22") (pintype "input"))
      (node (ref "X3") (pin "3") (pinfunction "TMDS_DATA2_N_3") (pintype "bidirectional"))
    )
    (net (code "63") (name "HDMI_TX_DATA2_P") (class "Default")
      (node (ref "U2") (pin "P62") (pinfunction "IO_L12P_D1_MISO2_2_P62") (pintype "bidirectional"))
      (node (ref "U8") (pin "23") (pinfunction "D2+_23") (pintype "input"))
      (node (ref "X3") (pin "1") (pinfunction "TMDS_DATA2_P_1") (pintype "bidirectional"))
    )
    (net (code "64") (name "HDMI_TX_HPD") (class "Default")
      (node (ref "U8") (pin "10") (pinfunction "HPD_B_10") (pintype "input"))
      (node (ref "X3") (pin "19") (pinfunction "HPD/HEAC_N_19") (pintype "bidirectional"))
    )
    (net (code "65") (name "HDMI_TX_HPD_3V3") (class "Default")
      (node (ref "U2") (pin "P43") (pinfunction "IO_L62N_D6_2_P43") (pintype "bidirectional"))
      (node (ref "U8") (pin "4") (pinfunction "HPD_A_4") (pintype "output"))
    )
    (net (code "66") (name "HDMI_TX_SCL") (class "Default")
      (node (ref "U8") (pin "8") (pinfunction "SCL_B_8") (pintype "input"))
      (node (ref "X3") (pin "15") (pinfunction "SCL_15") (pintype "bidirectional"))
    )
    (net (code "67") (name "HDMI_TX_SCL_3V3") (class "Default")
      (node (ref "U2") (pin "P46") (pinfunction "IO_L49P_D3_2_P46") (pintype "bidirectional"))
      (node (ref "U8") (pin "2") (pinfunction "SCL_A_2") (pintype "output"))
    )
    (net (code "68") (name "HDMI_TX_SDA") (class "Default")
      (node (ref "U8") (pin "9") (pinfunction "SDA_B_9") (pintype "input"))
      (node (ref "X3") (pin "16") (pinfunction "SDA_16") (pintype "bidirectional"))
    )
    (net (code "69") (name "HDMI_TX_SDA_3V3") (class "Default")
      (node (ref "U2") (pin "P45") (pinfunction "IO_L49N_D4_2_P45") (pintype "bidirectional"))
      (node (ref "U8") (pin "3") (pinfunction "SDA_A_3") (pintype "output"))
    )
    (net (code "70") (name "LEDS0_CLK") (class "Default")
      (node (ref "U2") (pin "P81") (pinfunction "IO_L46P_1_P81") (pintype "bidirectional"))
      (node (ref "U7") (pin "5") (pinfunction "A4_5") (pintype "bidirectional"))
    )
    (net (code "71") (name "LEDS0_CLK_5V") (class "Default")
      (node (ref "RN3") (pin "8") (pinfunction "8_8") (pintype "passive"))
      (node (ref "SV4") (pin "3") (pinfunction "3_3") (pintype "passive"))
      (node (ref "U7") (pin "10") (pinfunction "B4_10") (pintype "bidirectional"))
    )
    (net (code "72") (name "LEDS0_DATA") (class "Default")
      (node (ref "U2") (pin "P80") (pinfunction "IO_L46N_1_P80") (pintype "bidirectional"))
      (node (ref "U7") (pin "4") (pinfunction "A3_4") (pintype "bidirectional"))
    )
    (net (code "73") (name "LEDS0_DATA_5V") (class "Default")
      (node (ref "RN3") (pin "7") (pinfunction "7_7") (pintype "passive"))
      (node (ref "SV4") (pin "2") (pinfunction "2_2") (pintype "passive"))
      (node (ref "U7") (pin "11") (pinfunction "B3_11") (pintype "bidirectional"))
    )
    (net (code "74") (name "LEDS1_CLK") (class "Default")
      (node (ref "U2") (pin "P79") (pinfunction "IO_L47P_1_P79") (pintype "bidirectional"))
      (node (ref "U7") (pin "3") (pinfunction "A2_3") (pintype "bidirectional"))
    )
    (net (code "75") (name "LEDS1_CLK_5V") (class "Default")
      (node (ref "RN3") (pin "6") (pinfunction "6_6") (pintype "passive"))
      (node (ref "SV3") (pin "3") (pinfunction "3_3") (pintype "passive"))
      (node (ref "U7") (pin "12") (pinfunction "B2_12") (pintype "bidirectional"))
    )
    (net (code "76") (name "LEDS1_DATA") (class "Default")
      (node (ref "U2") (pin "P78") (pinfunction "IO_L47N_1_P78") (pintype "bidirectional"))
      (node (ref "U7") (pin "2") (pinfunction "A1_2") (pintype "bidirectional"))
    )
    (net (code "77") (name "LEDS1_DATA_5V") (class "Default")
      (node (ref "RN3") (pin "5") (pinfunction "5_5") (pintype "passive"))
      (node (ref "SV3") (pin "2") (pinfunction "2_2") (pintype "passive"))
      (node (ref "U7") (pin "13") (pinfunction "B1_13") (pintype "bidirectional"))
    )
    (net (code "78") (name "Net-(JP2-Pad2)") (class "Default")
      (node (ref "JP2") (pin "2") (pinfunction "2_2") (pintype "passive"))
      (node (ref "X5") (pin "12") (pinfunction "12_12") (pintype "passive"))
      (node (ref "X5") (pin "6") (pinfunction "6_6") (pintype "passive"))
    )
    (net (code "79") (name "Net-(JP3-Pad2)") (class "Default")
      (node (ref "JP3") (pin "2") (pinfunction "2_2") (pintype "passive"))
      (node (ref "X6") (pin "12") (pinfunction "12_12") (pintype "passive"))
      (node (ref "X6") (pin "6") (pinfunction "6_6") (pintype "passive"))
    )
    (net (code "80") (name "Net-(LED1-PadA)") (class "Default")
      (node (ref "LED1") (pin "A") (pinfunction "A_A") (pintype "passive"))
      (node (ref "R4") (pin "1") (pinfunction "1_1") (pintype "passive"))
    )
    (net (code "81") (name "Net-(U2A-IO_L1P_HSWAPEN_0)") (class "Default")
      (node (ref "R13") (pin "1") (pinfunction "1_1") (pintype "passive"))
      (node (ref "U2") (pin "P144") (pinfunction "IO_L1P_HSWAPEN_0_P144") (pintype "bidirectional"))
    )
    (net (code "82") (name "Net-(U2C-IO_L1P_CCLK_2)") (class "Default")
      (node (ref "R19") (pin "2") (pinfunction "2_2") (pintype "passive"))
      (node (ref "R20") (pin "1") (pinfunction "1_1") (pintype "passive"))
      (node (ref "U2") (pin "P70") (pinfunction "IO_L1P_CCLK_2_P70") (pintype "bidirectional"))
      (node (ref "U9") (pin "6") (pinfunction "C_6") (pintype "input"))
    )
    (net (code "83") (name "Net-(U2C-IO_L3N_MOSI_CSI_B_MISO0_2)") (class "Default")
      (node (ref "U2") (pin "P64") (pinfunction "IO_L3N_MOSI_CSI_B_MISO0_2_P64") (pintype "bidirectional"))
      (node (ref "U9") (pin "5") (pinfunction "DQ0_5") (pintype "input"))
    )
    (net (code "84") (name "Net-(U2C-IO_L3P_D0_DIN_MISO_MISO1_2)") (class "Default")
      (node (ref "U2") (pin "P65") (pinfunction "IO_L3P_D0_DIN_MISO_MISO1_2_P65") (pintype "bidirectional"))
      (node (ref "U9") (pin "2") (pinfunction "DQ1_2") (pintype "output"))
    )
    (net (code "85") (name "Net-(U2C-IO_L65N_CSO_B_2)") (class "Default")
      (node (ref "R21") (pin "1") (pinfunction "1_1") (pintype "passive"))
      (node (ref "U2") (pin "P38") (pinfunction "IO_L65N_CSO_B_2_P38") (pintype "bidirectional"))
      (node (ref "U9") (pin "1") (pinfunction "S#_1") (pintype "input"))
    )
    (net (code "86") (name "Net-(U2C-IO_L65P_INIT_B_2)") (class "Default")
      (node (ref "R16") (pin "1") (pinfunction "1_1") (pintype "passive"))
      (node (ref "U2") (pin "P39") (pinfunction "IO_L65P_INIT_B_2_P39") (pintype "bidirectional"))
    )
    (net (code "87") (name "Net-(U2C-PROGRAM_B_2)") (class "Default")
      (node (ref "R18") (pin "1") (pinfunction "1_1") (pintype "passive"))
      (node (ref "U2") (pin "P37") (pinfunction "PROGRAM_B_2_P37") (pintype "input"))
    )
    (net (code "88") (name "Net-(U3-CLK)") (class "Default")
      (node (ref "R6") (pin "1") (pinfunction "1_1") (pintype "passive"))
      (node (ref "U3") (pin "4") (pinfunction "CLK_4") (pintype "input"))
      (node (ref "U4") (pin "62") (pinfunction "EESK_62") (pintype "output"))
    )
    (net (code "89") (name "Net-(U3-CS)") (class "Default")
      (node (ref "R5") (pin "1") (pinfunction "1_1") (pintype "passive"))
      (node (ref "U3") (pin "5") (pinfunction "CS_5") (pintype "input"))
      (node (ref "U4") (pin "63") (pinfunction "EECS_63") (pintype "output"))
    )
    (net (code "90") (name "Net-(U3-DI)") (class "Default")
      (node (ref "R8") (pin "2") (pinfunction "2_2") (pintype "passive"))
      (node (ref "U3") (pin "3") (pinfunction "DI_3") (pintype "input"))
      (node (ref "U4") (pin "61") (pinfunction "EEDATA_61") (pintype "input"))
    )
    (net (code "91") (name "Net-(U3-DO)") (class "Default")
      (node (ref "R7") (pin "1") (pinfunction "1_1") (pintype "passive"))
      (node (ref "R8") (pin "1") (pinfunction "1_1") (pintype "passive"))
      (node (ref "U3") (pin "1") (pinfunction "DO_1") (pintype "output"))
    )
    (net (code "92") (name "Net-(U4--RESET)") (class "Default")
      (node (ref "R10") (pin "2") (pinfunction "2_2") (pintype "passive"))
      (node (ref "U4") (pin "14") (pinfunction "-RESET_14") (pintype "input"))
    )
    (net (code "93") (name "Net-(U4-D+)") (class "Default")
      (node (ref "U4") (pin "8") (pinfunction "D+_8") (pintype "bidirectional"))
      (node (ref "X1") (pin "D+") (pinfunction "D+_D+") (pintype "bidirectional"))
    )
    (net (code "94") (name "Net-(U4-D-)") (class "Default")
      (node (ref "U4") (pin "7") (pinfunction "D-_7") (pintype "bidirectional"))
      (node (ref "X1") (pin "D-") (pinfunction "D-_D-") (pintype "bidirectional"))
    )
    (net (code "95") (name "Net-(U4-REF)") (class "Default")
      (node (ref "R9") (pin "2") (pinfunction "2_2") (pintype "passive"))
      (node (ref "U4") (pin "6") (pinfunction "REF_6") (pintype "input"))
    )
    (net (code "96") (name "Net-(U4-VPHY)") (class "Default")
      (node (ref "C20") (pin "1") (pinfunction "1_1") (pintype "passive"))
      (node (ref "C21") (pin "1") (pinfunction "1_1") (pintype "passive"))
      (node (ref "FB1") (pin "2") (pinfunction "2_2") (pintype "passive"))
      (node (ref "U4") (pin "4") (pinfunction "VPHY_4") (pintype "power_in"))
    )
    (net (code "97") (name "Net-(U4-VPLL)") (class "Default")
      (node (ref "C17") (pin "1") (pinfunction "1_1") (pintype "passive"))
      (node (ref "C19") (pin "1") (pinfunction "1_1") (pintype "passive"))
      (node (ref "FB2") (pin "2") (pinfunction "2_2") (pintype "passive"))
      (node (ref "U4") (pin "9") (pinfunction "VPLL_9") (pintype "power_in"))
    )
    (net (code "98") (name "Net-(U4-XTIN)") (class "Default")
      (node (ref "C23") (pin "1") (pinfunction "1_1") (pintype "passive"))
      (node (ref "U4") (pin "2") (pinfunction "XTIN_2") (pintype "input"))
      (node (ref "Y1") (pin "3") (pinfunction "OUT_3") (pintype "bidirectional"))
    )
    (net (code "99") (name "Net-(U4-XTOUT)") (class "Default")
      (node (ref "C18") (pin "1") (pinfunction "1_1") (pintype "passive"))
      (node (ref "U4") (pin "3") (pinfunction "XTOUT_3") (pintype "output"))
      (node (ref "Y1") (pin "1") (pinfunction "IN_1") (pintype "bidirectional"))
    )
    (net (code "100") (name "Net-(U12-SW1)") (class "Default")
      (node (ref "C57") (pin "2") (pinfunction "2_2") (pintype "passive"))
      (node (ref "L3") (pin "1") (pinfunction "1_1") (pintype "passive"))
      (node (ref "U12") (pin "3") (pinfunction "SW1_3") (pintype "bidirectional"))
    )
    (net (code "101") (name "Net-(U12-SW2)") (class "Default")
      (node (ref "C59") (pin "2") (pinfunction "2_2") (pintype "passive"))
      (node (ref "L4") (pin "1") (pinfunction "1_1") (pintype "passive"))
      (node (ref "U12") (pin "14") (pinfunction "SW2_14") (pintype "bidirectional"))
    )
    (net (code "102") (name "Net-(U12-VBST1)") (class "Default")
      (node (ref "C57") (pin "1") (pinfunction "1_1") (pintype "passive"))
      (node (ref "U12") (pin "2") (pinfunction "VBST1_2") (pintype "input"))
    )
    (net (code "103") (name "Net-(U12-VBST2)") (class "Default")
      (node (ref "C59") (pin "1") (pinfunction "1_1") (pintype "passive"))
      (node (ref "U12") (pin "15") (pinfunction "VBST2_15") (pintype "input"))
    )
    (net (code "104") (name "Net-(U12-VFB1)") (class "Default")
      (node (ref "R26") (pin "1") (pinfunction "1_1") (pintype "passive"))
      (node (ref "R27") (pin "1") (pinfunction "1_1") (pintype "passive"))
      (node (ref "U12") (pin "7") (pinfunction "VFB1_7") (pintype "input"))
    )
    (net (code "105") (name "Net-(U12-VFB2)") (class "Default")
      (node (ref "R28") (pin "1") (pinfunction "1_1") (pintype "passive"))
      (node (ref "R29") (pin "1") (pinfunction "1_1") (pintype "passive"))
      (node (ref "U12") (pin "10") (pinfunction "VFB2_10") (pintype "input"))
    )
    (net (code "106") (name "Net-(U12-VREG5)") (class "Default")
      (node (ref "C56") (pin "1") (pinfunction "1_1") (pintype "passive"))
      (node (ref "U12") (pin "9") (pinfunction "VREG5_9") (pintype "power_in"))
    )
    (net (code "107") (name "Net-(X2-HPD{slash}HEAC_N)") (class "Default")
      (node (ref "R15") (pin "2") (pinfunction "2_2") (pintype "passive"))
      (node (ref "X2") (pin "19") (pinfunction "HPD/HEAC_N_19") (pintype "bidirectional"))
    )
    (net (code "108") (name "Net-(X4-HPD{slash}HEAC_N)") (class "Default")
      (node (ref "R23") (pin "2") (pinfunction "2_2") (pintype "passive"))
      (node (ref "X4") (pin "19") (pinfunction "HPD/HEAC_N_19") (pintype "bidirectional"))
    )
    (net (code "109") (name "PMOD0_0") (class "Default")
      (node (ref "U2") (pin "P104") (pinfunction "IO_L1N_VREF_1_P104") (pintype "bidirectional"))
      (node (ref "X6") (pin "1") (pinfunction "1_1") (pintype "passive"))
    )
    (net (code "110") (name "PMOD0_1") (class "Default")
      (node (ref "U2") (pin "P101") (pinfunction "IO_L32N_1_P101") (pintype "bidirectional"))
      (node (ref "X6") (pin "2") (pinfunction "2_2") (pintype "passive"))
    )
    (net (code "111") (name "PMOD0_2") (class "Default")
      (node (ref "U2") (pin "P99") (pinfunction "IO_L33N_1_P99") (pintype "bidirectional"))
      (node (ref "X6") (pin "3") (pinfunction "3_3") (pintype "passive"))
    )
    (net (code "112") (name "PMOD0_3") (class "Default")
      (node (ref "U2") (pin "P97") (pinfunction "IO_L34N_1_P97") (pintype "bidirectional"))
      (node (ref "X6") (pin "4") (pinfunction "4_4") (pintype "passive"))
    )
    (net (code "113") (name "PMOD1_0") (class "Default")
      (node (ref "U2") (pin "P105") (pinfunction "IO_L1P_1_P105") (pintype "bidirectional"))
      (node (ref "X6") (pin "7") (pinfunction "7_7") (pintype "passive"))
    )
    (net (code "114") (name "PMOD1_1") (class "Default")
      (node (ref "U2") (pin "P102") (pinfunction "IO_L32P_1_P102") (pintype "bidirectional"))
      (node (ref "X6") (pin "8") (pinfunction "8_8") (pintype "passive"))
    )
    (net (code "115") (name "PMOD1_2") (class "Default")
      (node (ref "U2") (pin "P100") (pinfunction "IO_L33P_1_P100") (pintype "bidirectional"))
      (node (ref "X6") (pin "9") (pinfunction "9_9") (pintype "passive"))
    )
    (net (code "116") (name "PMOD1_3") (class "Default")
      (node (ref "U2") (pin "P98") (pinfunction "IO_L34P_1_P98") (pintype "bidirectional"))
      (node (ref "X6") (pin "10") (pinfunction "10_10") (pintype "passive"))
    )
    (net (code "117") (name "PMOD2_0") (class "Default")
      (node (ref "U2") (pin "P118") (pinfunction "IO_L63N_SCP6_0_P118") (pintype "bidirectional"))
      (node (ref "X5") (pin "1") (pinfunction "1_1") (pintype "passive"))
    )
    (net (code "118") (name "PMOD2_1") (class "Default")
      (node (ref "U2") (pin "P116") (pinfunction "IO_L64N_SCP4_0_P116") (pintype "bidirectional"))
      (node (ref "X5") (pin "2") (pinfunction "2_2") (pintype "passive"))
    )
    (net (code "119") (name "PMOD2_2") (class "Default")
      (node (ref "U2") (pin "P114") (pinfunction "IO_L65N_SCP2_0_P114") (pintype "bidirectional"))
      (node (ref "X5") (pin "3") (pinfunction "3_3") (pintype "passive"))
    )
    (net (code "120") (name "PMOD2_3") (class "Default")
      (node (ref "U2") (pin "P111") (pinfunction "IO_L66N_SCP0_0_P111") (pintype "bidirectional"))
      (node (ref "X5") (pin "4") (pinfunction "4_4") (pintype "passive"))
    )
    (net (code "121") (name "PMOD3_0") (class "Default")
      (node (ref "U2") (pin "P119") (pinfunction "IO_L63P_SCP7_0_P119") (pintype "bidirectional"))
      (node (ref "X5") (pin "7") (pinfunction "7_7") (pintype "passive"))
    )
    (net (code "122") (name "PMOD3_1") (class "Default")
      (node (ref "U2") (pin "P117") (pinfunction "IO_L64P_SCP5_0_P117") (pintype "bidirectional"))
      (node (ref "X5") (pin "8") (pinfunction "8_8") (pintype "passive"))
    )
    (net (code "123") (name "PMOD3_2") (class "Default")
      (node (ref "U2") (pin "P115") (pinfunction "IO_L65P_SCP3_0_P115") (pintype "bidirectional"))
      (node (ref "X5") (pin "9") (pinfunction "9_9") (pintype "passive"))
    )
    (net (code "124") (name "PMOD3_3") (class "Default")
      (node (ref "U2") (pin "P112") (pinfunction "IO_L66P_SCP1_0_P112") (pintype "bidirectional"))
      (node (ref "X5") (pin "10") (pinfunction "10_10") (pintype "passive"))
    )
    (net (code "125") (name "USB_CTS#") (class "Default")
      (node (ref "U2") (pin "P92") (pinfunction "IO_L41N_GCLK8_1_P92") (pintype "bidirectional"))
      (node (ref "U4") (pin "41") (pinfunction "BDBUS3_41") (pintype "bidirectional"))
    )
    (net (code "126") (name "USB_DCD#") (class "Default")
      (node (ref "U2") (pin "P83") (pinfunction "IO_L45P_1_P83") (pintype "bidirectional"))
      (node (ref "U4") (pin "45") (pinfunction "BDBUS6_45") (pintype "bidirectional"))
    )
    (net (code "127") (name "USB_DSR#") (class "Default")
      (node (ref "U2") (pin "P84") (pinfunction "IO_L43N_GCLK4_1_P84") (pintype "bidirectional"))
      (node (ref "U4") (pin "44") (pinfunction "BDBUS5_44") (pintype "bidirectional"))
    )
    (net (code "128") (name "USB_DTR#") (class "Default")
      (node (ref "U2") (pin "P85") (pinfunction "IO_L43P_GCLK5_1_P85") (pintype "bidirectional"))
      (node (ref "U4") (pin "43") (pinfunction "BDBUS4_43") (pintype "bidirectional"))
    )
    (net (code "129") (name "USB_PWRSAVE#") (class "Default")
      (node (ref "R11") (pin "1") (pinfunction "1_1") (pintype "passive"))
      (node (ref "R12") (pin "2") (pinfunction "2_2") (pintype "passive"))
      (node (ref "U4") (pin "59") (pinfunction "PWRSAVE/BCBUS7_59") (pintype "bidirectional"))
    )
    (net (code "130") (name "USB_RI#") (class "Default")
      (node (ref "U2") (pin "P82") (pinfunction "IO_L45N_1_P82") (pintype "bidirectional"))
      (node (ref "U4") (pin "46") (pinfunction "BDBUS7_46") (pintype "bidirectional"))
    )
    (net (code "131") (name "USB_RTS#") (class "Default")
      (node (ref "U2") (pin "P93") (pinfunction "IO_L41P_GCLK9_IRDY1_1_P93") (pintype "bidirectional"))
      (node (ref "U4") (pin "40") (pinfunction "BDBUS2_40") (pintype "bidirectional"))
    )
    (net (code "132") (name "USB_RXD") (class "Default")
      (node (ref "U2") (pin "P94") (pinfunction "IO_L40N_GCLK10_1_P94") (pintype "bidirectional"))
      (node (ref "U4") (pin "39") (pinfunction "BDBUS1_39") (pintype "bidirectional"))
    )
    (net (code "133") (name "USB_TCK") (class "Default")
      (node (ref "SV2") (pin "3") (pinfunction "3_3") (pintype "passive"))
      (node (ref "U11") (pin "16") (pinfunction "IO13_16") (pintype "bidirectional"))
      (node (ref "U2") (pin "P109") (pinfunction "TCK_P109") (pintype "input"))
      (node (ref "U4") (pin "16") (pinfunction "ADBUS0_16") (pintype "bidirectional"))
    )
    (net (code "134") (name "USB_TDI") (class "Default")
      (node (ref "SV2") (pin "5") (pinfunction "5_5") (pintype "passive"))
      (node (ref "U2") (pin "P110") (pinfunction "TDI_P110") (pintype "input"))
      (node (ref "U4") (pin "17") (pinfunction "ADBUS1_17") (pintype "bidirectional"))
    )
    (net (code "135") (name "USB_TMS") (class "Default")
      (node (ref "SV2") (pin "6") (pinfunction "6_6") (pintype "passive"))
      (node (ref "U11") (pin "13") (pinfunction "IO14_13") (pintype "bidirectional"))
      (node (ref "U2") (pin "P107") (pinfunction "TMS_P107") (pintype "input"))
      (node (ref "U4") (pin "19") (pinfunction "ADBUS3_19") (pintype "bidirectional"))
    )
    (net (code "136") (name "USB_TXD") (class "Default")
      (node (ref "U2") (pin "P95") (pinfunction "IO_L40P_GCLK11_1_P95") (pintype "bidirectional"))
      (node (ref "U4") (pin "38") (pinfunction "BDBUS0_38") (pintype "bidirectional"))
    )
    (net (code "137") (name "USB_VBUS") (class "Default")
      (node (ref "JP1") (pin "3") (pinfunction "3_3") (pintype "passive"))
      (node (ref "R12") (pin "1") (pinfunction "1_1") (pintype "passive"))
      (node (ref "X1") (pin "VBUS") (pinfunction "VBUS_VBUS") (pintype "bidirectional"))
    )
    (net (code "138") (name "unconnected-(U2A-IO_L1N_VREF_0-PadP143)") (class "Default")
      (node (ref "U2") (pin "P143") (pinfunction "IO_L1N_VREF_0_P143") (pintype "bidirectional"))
    )
    (net (code "139") (name "unconnected-(U2A-IO_L35N_GCLK16_0-PadP131)") (class "Default")
      (node (ref "U2") (pin "P131") (pinfunction "IO_L35N_GCLK16_0_P131") (pintype "bidirectional"))
    )
    (net (code "140") (name "unconnected-(U2A-IO_L35P_GCLK17_0-PadP132)") (class "Default")
      (node (ref "U2") (pin "P132") (pinfunction "IO_L35P_GCLK17_0_P132") (pintype "bidirectional"))
    )
    (net (code "141") (name "unconnected-(U2A-IO_L62N_VREF_0-PadP120)") (class "Default")
      (node (ref "U2") (pin "P120") (pinfunction "IO_L62N_VREF_0_P120") (pintype "bidirectional"))
    )
    (net (code "142") (name "unconnected-(U2B-IO_L42P_GCLK7_1-PadP88)") (class "Default")
      (node (ref "U2") (pin "P88") (pinfunction "IO_L42P_GCLK7_1_P88") (pintype "bidirectional"))
    )
    (net (code "143") (name "unconnected-(U2B-IO_L74N_DOUT_BUSY_1-PadP74)") (class "Default")
      (node (ref "U2") (pin "P74") (pinfunction "IO_L74N_DOUT_BUSY_1_P74") (pintype "bidirectional"))
    )
    (net (code "144") (name "unconnected-(U2B-IO_L74P_AWAKE_1-PadP75)") (class "Default")
      (node (ref "U2") (pin "P75") (pinfunction "IO_L74P_AWAKE_1_P75") (pintype "bidirectional"))
    )
    (net (code "145") (name "unconnected-(U2C-CMPCS_B_2-PadP72)") (class "Default")
      (node (ref "U2") (pin "P72") (pinfunction "CMPCS_B_2_P72") (pintype "bidirectional"))
    )
    (net (code "146") (name "unconnected-(U2C-DONE_2-PadP71)") (class "Default")
      (node (ref "U2") (pin "P71") (pinfunction "DONE_2_P71") (pintype "bidirectional"))
    )
    (net (code "147") (name "unconnected-(U2C-IO_L2N_CMPMOSI_2-PadP66)") (class "Default")
      (node (ref "U2") (pin "P66") (pinfunction "IO_L2N_CMPMOSI_2_P66") (pintype "bidirectional"))
    )
    (net (code "148") (name "unconnected-(U2C-IO_L2P_CMPCLK_2-PadP67)") (class "Default")
      (node (ref "U2") (pin "P67") (pinfunction "IO_L2P_CMPCLK_2_P67") (pintype "bidirectional"))
    )
    (net (code "149") (name "unconnected-(U2C-IO_L13N_D10_2-PadP59)") (class "Default")
      (node (ref "U2") (pin "P59") (pinfunction "IO_L13N_D10_2_P59") (pintype "bidirectional"))
    )
    (net (code "150") (name "unconnected-(U2C-IO_L48P_D7_2-PadP48)") (class "Default")
      (node (ref "U2") (pin "P48") (pinfunction "IO_L48P_D7_2_P48") (pintype "bidirectional"))
    )
    (net (code "151") (name "unconnected-(U2C-IO_L64N_D9_2-PadP40)") (class "Default")
      (node (ref "U2") (pin "P40") (pinfunction "IO_L64N_D9_2_P40") (pintype "bidirectional"))
    )
    (net (code "152") (name "unconnected-(U2C-IO_L64P_D8_2-PadP41)") (class "Default")
      (node (ref "U2") (pin "P41") (pinfunction "IO_L64P_D8_2_P41") (pintype "bidirectional"))
    )
    (net (code "153") (name "unconnected-(U2D-IO_L1N_VREF_3-PadP34)") (class "Default")
      (node (ref "U2") (pin "P34") (pinfunction "IO_L1N_VREF_3_P34") (pintype "bidirectional"))
    )
    (net (code "154") (name "unconnected-(U2D-IO_L1P_3-PadP35)") (class "Default")
      (node (ref "U2") (pin "P35") (pinfunction "IO_L1P_3_P35") (pintype "bidirectional"))
    )
    (net (code "155") (name "unconnected-(U2D-IO_L42N_GCLK24_3-PadP21)") (class "Default")
      (node (ref "U2") (pin "P21") (pinfunction "IO_L42N_GCLK24_3_P21") (pintype "bidirectional"))
    )
    (net (code "156") (name "unconnected-(U2D-IO_L42P_GCLK25_TRDY2_3-PadP22)") (class "Default")
      (node (ref "U2") (pin "P22") (pinfunction "IO_L42P_GCLK25_TRDY2_3_P22") (pintype "bidirectional"))
    )
    (net (code "157") (name "unconnected-(U2D-IO_L49N_3-PadP11)") (class "Default")
      (node (ref "U2") (pin "P11") (pinfunction "IO_L49N_3_P11") (pintype "bidirectional"))
    )
    (net (code "158") (name "unconnected-(U2D-IO_L50N_3-PadP9)") (class "Default")
      (node (ref "U2") (pin "P9") (pinfunction "IO_L50N_3_P9") (pintype "bidirectional"))
    )
    (net (code "159") (name "unconnected-(U2D-IO_L50P_3-PadP10)") (class "Default")
      (node (ref "U2") (pin "P10") (pinfunction "IO_L50P_3_P10") (pintype "bidirectional"))
    )
    (net (code "160") (name "unconnected-(U4--PWREN-Pad60)") (class "Default")
      (node (ref "U4") (pin "60") (pinfunction "-PWREN_60") (pintype "output"))
    )
    (net (code "161") (name "unconnected-(U4--SUSPEND-Pad36)") (class "Default")
      (node (ref "U4") (pin "36") (pinfunction "-SUSPEND_36") (pintype "output"))
    )
    (net (code "162") (name "unconnected-(U4-ACBUS0-Pad26)") (class "Default")
      (node (ref "U4") (pin "26") (pinfunction "ACBUS0_26") (pintype "bidirectional"))
    )
    (net (code "163") (name "unconnected-(U4-ACBUS1-Pad27)") (class "Default")
      (node (ref "U4") (pin "27") (pinfunction "ACBUS1_27") (pintype "bidirectional"))
    )
    (net (code "164") (name "unconnected-(U4-ACBUS2-Pad28)") (class "Default")
      (node (ref "U4") (pin "28") (pinfunction "ACBUS2_28") (pintype "bidirectional"))
    )
    (net (code "165") (name "unconnected-(U4-ACBUS3-Pad29)") (class "Default")
      (node (ref "U4") (pin "29") (pinfunction "ACBUS3_29") (pintype "bidirectional"))
    )
    (net (code "166") (name "unconnected-(U4-ACBUS4-Pad30)") (class "Default")
      (node (ref "U4") (pin "30") (pinfunction "ACBUS4_30") (pintype "bidirectional"))
    )
    (net (code "167") (name "unconnected-(U4-ACBUS5-Pad32)") (class "Default")
      (node (ref "U4") (pin "32") (pinfunction "ACBUS5_32") (pintype "bidirectional"))
    )
    (net (code "168") (name "unconnected-(U4-ACBUS6-Pad33)") (class "Default")
      (node (ref "U4") (pin "33") (pinfunction "ACBUS6_33") (pintype "bidirectional"))
    )
    (net (code "169") (name "unconnected-(U4-ACBUS7-Pad34)") (class "Default")
      (node (ref "U4") (pin "34") (pinfunction "ACBUS7_34") (pintype "bidirectional"))
    )
    (net (code "170") (name "unconnected-(U4-ADBUS4-Pad21)") (class "Default")
      (node (ref "U4") (pin "21") (pinfunction "ADBUS4_21") (pintype "bidirectional"))
    )
    (net (code "171") (name "unconnected-(U4-ADBUS5-Pad22)") (class "Default")
      (node (ref "U4") (pin "22") (pinfunction "ADBUS5_22") (pintype "bidirectional"))
    )
    (net (code "172") (name "unconnected-(U4-ADBUS6-Pad23)") (class "Default")
      (node (ref "U4") (pin "23") (pinfunction "ADBUS6_23") (pintype "bidirectional"))
    )
    (net (code "173") (name "unconnected-(U4-ADBUS7-Pad24)") (class "Default")
      (node (ref "U4") (pin "24") (pinfunction "ADBUS7_24") (pintype "bidirectional"))
    )
    (net (code "174") (name "unconnected-(U4-BCBUS0-Pad48)") (class "Default")
      (node (ref "U4") (pin "48") (pinfunction "BCBUS0_48") (pintype "bidirectional"))
    )
    (net (code "175") (name "unconnected-(U4-BCBUS1-Pad52)") (class "Default")
      (node (ref "U4") (pin "52") (pinfunction "BCBUS1_52") (pintype "bidirectional"))
    )
    (net (code "176") (name "unconnected-(U4-BCBUS2-Pad53)") (class "Default")
      (node (ref "U4") (pin "53") (pinfunction "BCBUS2_53") (pintype "bidirectional"))
    )
    (net (code "177") (name "unconnected-(U4-BCBUS3-Pad54)") (class "Default")
      (node (ref "U4") (pin "54") (pinfunction "BCBUS3_54") (pintype "bidirectional"))
    )
    (net (code "178") (name "unconnected-(U4-BCBUS4-Pad55)") (class "Default")
      (node (ref "U4") (pin "55") (pinfunction "BCBUS4_55") (pintype "bidirectional"))
    )
    (net (code "179") (name "unconnected-(U4-BCBUS5-Pad57)") (class "Default")
      (node (ref "U4") (pin "57") (pinfunction "BCBUS5_57") (pintype "bidirectional"))
    )
    (net (code "180") (name "unconnected-(U4-BCBUS6-Pad58)") (class "Default")
      (node (ref "U4") (pin "58") (pinfunction "BCBUS6_58") (pintype "bidirectional"))
    )
    (net (code "181") (name "unconnected-(U7-NC-Pad6)") (class "Default")
      (node (ref "U7") (pin "6") (pinfunction "NC_6") (pintype "no_connect"))
    )
    (net (code "182") (name "unconnected-(U7-NC-Pad9)") (class "Default")
      (node (ref "U7") (pin "9") (pinfunction "NC_9") (pintype "no_connect"))
    )
    (net (code "183") (name "unconnected-(U11-IO2-Pad24)") (class "Default")
      (node (ref "U11") (pin "24") (pinfunction "IO2_24") (pintype "bidirectional"))
    )
    (net (code "184") (name "unconnected-(U11-IO4-Pad26)") (class "Default")
      (node (ref "U11") (pin "26") (pinfunction "IO4_26") (pintype "bidirectional"))
    )
    (net (code "185") (name "unconnected-(U11-IO5-Pad29)") (class "Default")
      (node (ref "U11") (pin "29") (pinfunction "IO5_29") (pintype "bidirectional"))
    )
    (net (code "186") (name "unconnected-(U11-IO18-Pad30)") (class "Default")
      (node (ref "U11") (pin "30") (pinfunction "IO18_30") (pintype "bidirectional"))
    )
    (net (code "187") (name "unconnected-(U11-IO19-Pad31)") (class "Default")
      (node (ref "U11") (pin "31") (pinfunction "IO19_31") (pintype "bidirectional"))
    )
    (net (code "188") (name "unconnected-(U11-IO21-Pad33)") (class "Default")
      (node (ref "U11") (pin "33") (pinfunction "IO21_33") (pintype "bidirectional"))
    )
    (net (code "189") (name "unconnected-(U11-IO22-Pad36)") (class "Default")
      (node (ref "U11") (pin "36") (pinfunction "IO22_36") (pintype "bidirectional"))
    )
    (net (code "190") (name "unconnected-(U11-IO23-Pad37)") (class "Default")
      (node (ref "U11") (pin "37") (pinfunction "IO23_37") (pintype "bidirectional"))
    )
    (net (code "191") (name "unconnected-(U11-IO25-Pad10)") (class "Default")
      (node (ref "U11") (pin "10") (pinfunction "IO25_10") (pintype "bidirectional"))
    )
    (net (code "192") (name "unconnected-(U11-IO26-Pad11)") (class "Default")
      (node (ref "U11") (pin "11") (pinfunction "IO26_11") (pintype "bidirectional"))
    )
    (net (code "193") (name "unconnected-(U11-IO27-Pad12)") (class "Default")
      (node (ref "U11") (pin "12") (pinfunction "IO27_12") (pintype "bidirectional"))
    )
    (net (code "194") (name "unconnected-(U11-IO32-Pad8)") (class "Default")
      (node (ref "U11") (pin "8") (pinfunction "IO32_8") (pintype "bidirectional"))
    )
    (net (code "195") (name "unconnected-(U11-IO33-Pad9)") (class "Default")
      (node (ref "U11") (pin "9") (pinfunction "IO33_9") (pintype "bidirectional"))
    )
    (net (code "196") (name "unconnected-(U11-IO34-Pad6)") (class "Default")
      (node (ref "U11") (pin "6") (pinfunction "IO34_6") (pintype "bidirectional"))
    )
    (net (code "197") (name "unconnected-(U11-IO35-Pad7)") (class "Default")
      (node (ref "U11") (pin "7") (pinfunction "IO35_7") (pintype "bidirectional"))
    )
    (net (code "198") (name "unconnected-(U11-NC-Pad32)") (class "Default")
      (node (ref "U11") (pin "32") (pinfunction "NC_32") (pintype "no_connect"))
    )
    (net (code "199") (name "unconnected-(U11-RXD0-Pad34)") (class "Default")
      (node (ref "U11") (pin "34") (pinfunction "RXD0_34") (pintype "bidirectional"))
    )
    (net (code "200") (name "unconnected-(U11-SCK{slash}CLK-Pad20)") (class "Default")
      (node (ref "U11") (pin "20") (pinfunction "SCK/CLK_20") (pintype "bidirectional"))
    )
    (net (code "201") (name "unconnected-(U11-SCS{slash}CMD-Pad19)") (class "Default")
      (node (ref "U11") (pin "19") (pinfunction "SCS/CMD_19") (pintype "bidirectional"))
    )
    (net (code "202") (name "unconnected-(U11-SENSOR_VN-Pad5)") (class "Default")
      (node (ref "U11") (pin "5") (pinfunction "SENSOR_VN_5") (pintype "input"))
    )
    (net (code "203") (name "unconnected-(U11-SENSOR_VP-Pad4)") (class "Default")
      (node (ref "U11") (pin "4") (pinfunction "SENSOR_VP_4") (pintype "input"))
    )
    (net (code "204") (name "unconnected-(U11-SHD{slash}SD2-Pad17)") (class "Default")
      (node (ref "U11") (pin "17") (pinfunction "SHD/SD2_17") (pintype "bidirectional"))
    )
    (net (code "205") (name "unconnected-(U11-SWP{slash}SD3-Pad18)") (class "Default")
      (node (ref "U11") (pin "18") (pinfunction "SWP/SD3_18") (pintype "bidirectional"))
    )
    (net (code "206") (name "unconnected-(U11-TXD0-Pad35)") (class "Default")
      (node (ref "U11") (pin "35") (pinfunction "TXD0_35") (pintype "bidirectional"))
    )
    (net (code "207") (name "unconnected-(U12-PG1-Pad6)") (class "Default")
      (node (ref "U12") (pin "6") (pinfunction "PG1_6") (pintype "output"))
    )
    (net (code "208") (name "unconnected-(U12-PG2-Pad11)") (class "Default")
      (node (ref "U12") (pin "11") (pinfunction "PG2_11") (pintype "output"))
    )
    (net (code "209") (name "unconnected-(U12-PadETP)") (class "Default")
      (node (ref "U12") (pin "ETP") (pinfunction "ETP_ETP") (pintype "no_connect"))
    )
    (net (code "210") (name "unconnected-(X2-PadSHIELD0)") (class "Default")
      (node (ref "X2") (pin "SHIELD0") (pinfunction "SHIELD0_SHIELD0") (pintype "no_connect"))
    )
    (net (code "211") (name "unconnected-(X2-PadSHIELD1)") (class "Default")
      (node (ref "X2") (pin "SHIELD1") (pinfunction "SHIELD1_SHIELD1") (pintype "no_connect"))
    )
    (net (code "212") (name "unconnected-(X2-PadSHIELD2)") (class "Default")
      (node (ref "X2") (pin "SHIELD2") (pinfunction "SHIELD2_SHIELD2") (pintype "no_connect"))
    )
    (net (code "213") (name "unconnected-(X2-PadSHIELD3)") (class "Default")
      (node (ref "X2") (pin "SHIELD3") (pinfunction "SHIELD3_SHIELD3") (pintype "no_connect"))
    )
    (net (code "214") (name "unconnected-(X3-PadSHIELD0)") (class "Default")
      (node (ref "X3") (pin "SHIELD0") (pinfunction "SHIELD0_SHIELD0") (pintype "no_connect"))
    )
    (net (code "215") (name "unconnected-(X3-PadSHIELD1)") (class "Default")
      (node (ref "X3") (pin "SHIELD1") (pinfunction "SHIELD1_SHIELD1") (pintype "no_connect"))
    )
    (net (code "216") (name "unconnected-(X3-PadSHIELD2)") (class "Default")
      (node (ref "X3") (pin "SHIELD2") (pinfunction "SHIELD2_SHIELD2") (pintype "no_connect"))
    )
    (net (code "217") (name "unconnected-(X3-PadSHIELD3)") (class "Default")
      (node (ref "X3") (pin "SHIELD3") (pinfunction "SHIELD3_SHIELD3") (pintype "no_connect"))
    )
    (net (code "218") (name "unconnected-(X4-PadSHIELD0)") (class "Default")
      (node (ref "X4") (pin "SHIELD0") (pinfunction "SHIELD0_SHIELD0") (pintype "no_connect"))
    )
    (net (code "219") (name "unconnected-(X4-PadSHIELD1)") (class "Default")
      (node (ref "X4") (pin "SHIELD1") (pinfunction "SHIELD1_SHIELD1") (pintype "no_connect"))
    )
    (net (code "220") (name "unconnected-(X4-PadSHIELD2)") (class "Default")
      (node (ref "X4") (pin "SHIELD2") (pinfunction "SHIELD2_SHIELD2") (pintype "no_connect"))
    )
    (net (code "221") (name "unconnected-(X4-PadSHIELD3)") (class "Default")
      (node (ref "X4") (pin "SHIELD3") (pinfunction "SHIELD3_SHIELD3") (pintype "no_connect"))
    )
  )
)
